# 2d.net
KiCad netlist of a schematic drawn in EAGLE
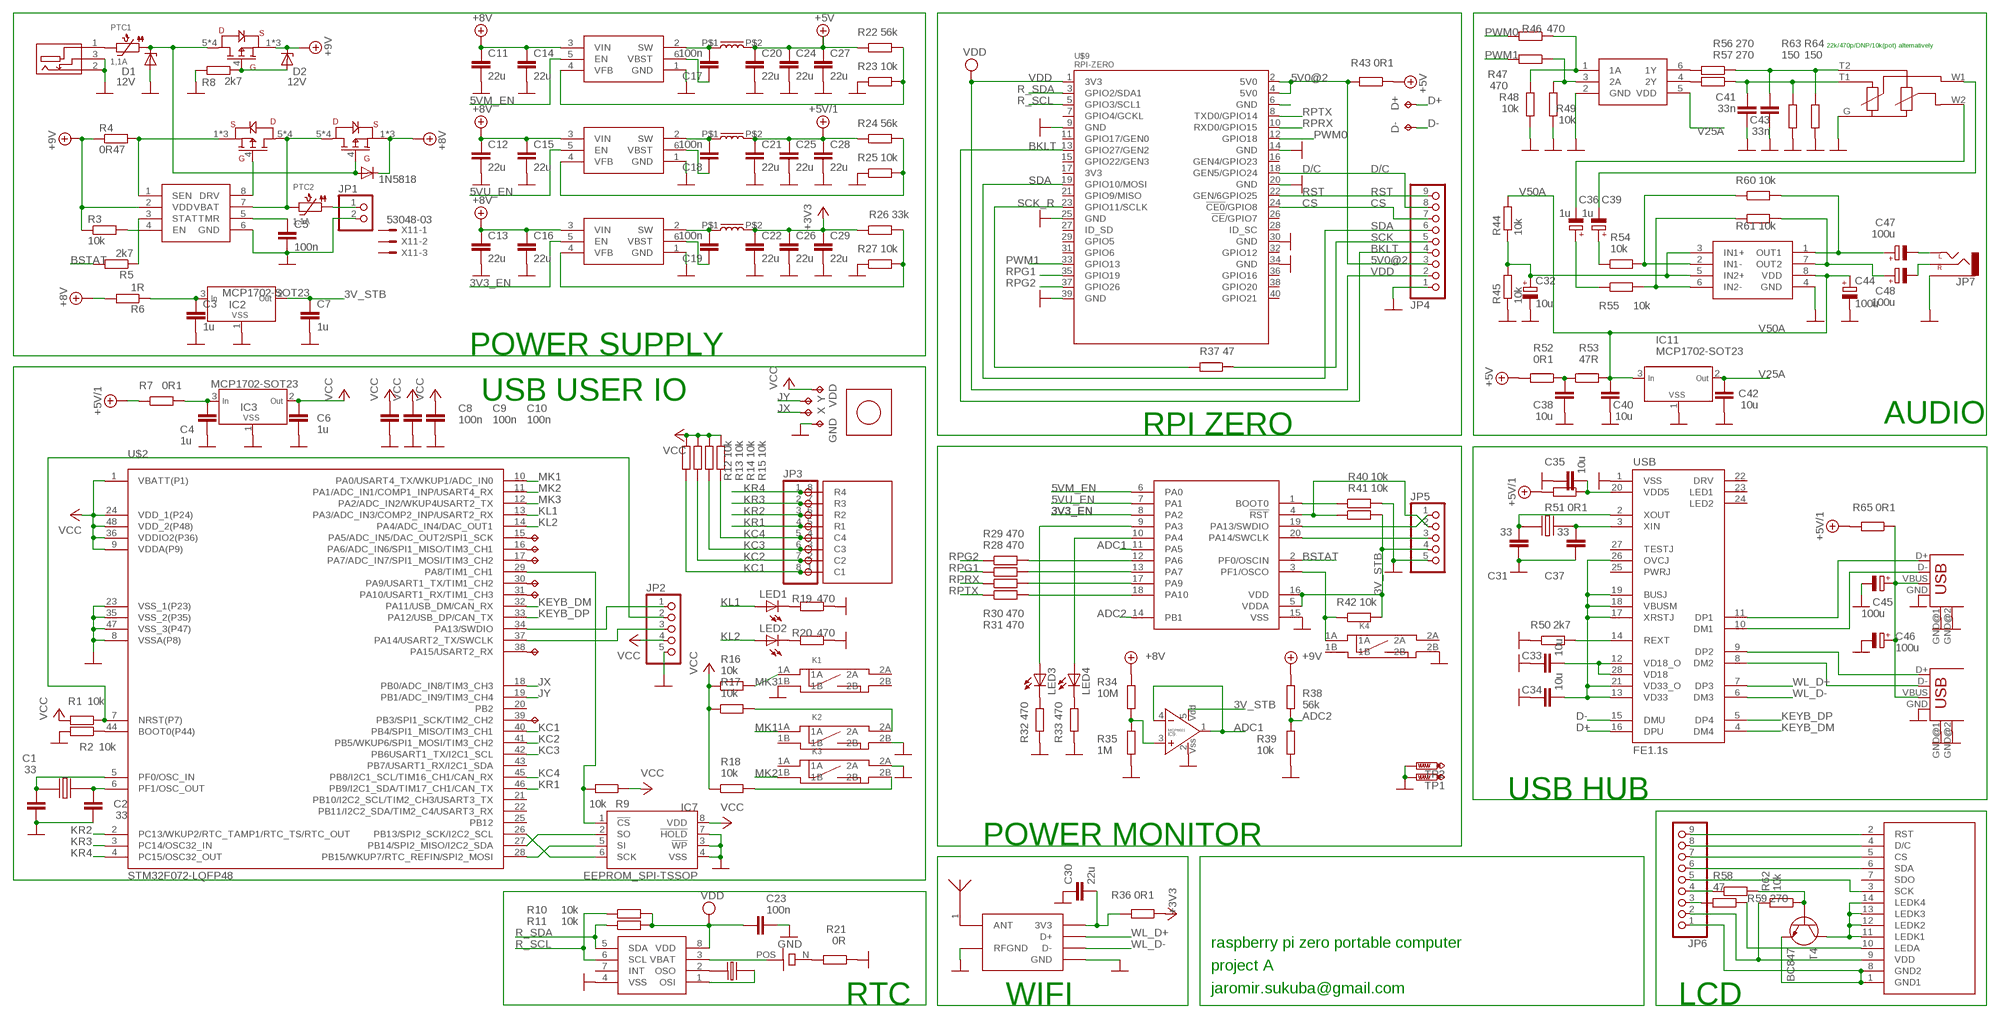
[diagram p0: schematic, sheet 1]

(export (version "E")
  (design (tool "Eeschema 10.0.6"))
  (components
    (comp (ref "ANT1")
      (value "ANT_RAINSUN_24GHZ")
      (footprint "eagle-import:ANT_RAINSUN-24G")
      (libsource (lib "eagle-import") (part "ANT_RAINSUN_24GHZ"))
    )
    (comp (ref "C1")
      (value "33")
      (footprint "eagle-import:R0805")
      (libsource (lib "eagle-import") (part "C_0806"))
    )
    (comp (ref "C2")
      (value "33")
      (footprint "eagle-import:R0805")
      (libsource (lib "eagle-import") (part "C_0806"))
    )
    (comp (ref "C3")
      (value "1u")
      (footprint "eagle-import:R0805")
      (libsource (lib "eagle-import") (part "C_0806"))
    )
    (comp (ref "C4")
      (value "1u")
      (footprint "eagle-import:R0805")
      (libsource (lib "eagle-import") (part "C_0806"))
    )
    (comp (ref "C5")
      (value "100n")
      (footprint "eagle-import:R0805")
      (libsource (lib "eagle-import") (part "C_0806"))
    )
    (comp (ref "C6")
      (value "1u")
      (footprint "eagle-import:R0805")
      (libsource (lib "eagle-import") (part "C_0806"))
    )
    (comp (ref "C7")
      (value "1u")
      (footprint "eagle-import:R0805")
      (libsource (lib "eagle-import") (part "C_0806"))
    )
    (comp (ref "C8")
      (value "100n")
      (footprint "eagle-import:R0805")
      (libsource (lib "eagle-import") (part "C_0806"))
    )
    (comp (ref "C9")
      (value "100n")
      (footprint "eagle-import:R0805")
      (libsource (lib "eagle-import") (part "C_0806"))
    )
    (comp (ref "C10")
      (value "100n")
      (footprint "eagle-import:R0805")
      (libsource (lib "eagle-import") (part "C_0806"))
    )
    (comp (ref "C11")
      (value "22u")
      (footprint "eagle-import:R0805")
      (libsource (lib "eagle-import") (part "C_0806"))
    )
    (comp (ref "C12")
      (value "22u")
      (footprint "eagle-import:R0805")
      (libsource (lib "eagle-import") (part "C_0806"))
    )
    (comp (ref "C13")
      (value "22u")
      (footprint "eagle-import:R0805")
      (libsource (lib "eagle-import") (part "C_0806"))
    )
    (comp (ref "C14")
      (value "22u")
      (footprint "eagle-import:R0805")
      (libsource (lib "eagle-import") (part "C_0806"))
    )
    (comp (ref "C15")
      (value "22u")
      (footprint "eagle-import:R0805")
      (libsource (lib "eagle-import") (part "C_0806"))
    )
    (comp (ref "C16")
      (value "22u")
      (footprint "eagle-import:R0805")
      (libsource (lib "eagle-import") (part "C_0806"))
    )
    (comp (ref "C17")
      (value "100n")
      (footprint "eagle-import:R0805")
      (libsource (lib "eagle-import") (part "C_0806"))
    )
    (comp (ref "C18")
      (value "100n")
      (footprint "eagle-import:R0805")
      (libsource (lib "eagle-import") (part "C_0806"))
    )
    (comp (ref "C19")
      (value "100n")
      (footprint "eagle-import:R0805")
      (libsource (lib "eagle-import") (part "C_0806"))
    )
    (comp (ref "C20")
      (value "22u")
      (footprint "eagle-import:R0805")
      (libsource (lib "eagle-import") (part "C_0806"))
    )
    (comp (ref "C21")
      (value "22u")
      (footprint "eagle-import:R0805")
      (libsource (lib "eagle-import") (part "C_0806"))
    )
    (comp (ref "C22")
      (value "22u")
      (footprint "eagle-import:R0805")
      (libsource (lib "eagle-import") (part "C_0806"))
    )
    (comp (ref "C23")
      (value "100n")
      (footprint "eagle-import:R0805")
      (libsource (lib "eagle-import") (part "C_0806"))
    )
    (comp (ref "C24")
      (value "22u")
      (footprint "eagle-import:R0805")
      (libsource (lib "eagle-import") (part "C_0806"))
    )
    (comp (ref "C25")
      (value "22u")
      (footprint "eagle-import:R0805")
      (libsource (lib "eagle-import") (part "C_0806"))
    )
    (comp (ref "C26")
      (value "22u")
      (footprint "eagle-import:R0805")
      (libsource (lib "eagle-import") (part "C_0806"))
    )
    (comp (ref "C27")
      (value "22u")
      (footprint "eagle-import:R0805")
      (libsource (lib "eagle-import") (part "C_0806"))
    )
    (comp (ref "C28")
      (value "22u")
      (footprint "eagle-import:R0805")
      (libsource (lib "eagle-import") (part "C_0806"))
    )
    (comp (ref "C29")
      (value "22u")
      (footprint "eagle-import:R0805")
      (libsource (lib "eagle-import") (part "C_0806"))
    )
    (comp (ref "C30")
      (value "22u")
      (footprint "eagle-import:R0805")
      (libsource (lib "eagle-import") (part "C_0806"))
    )
    (comp (ref "C31")
      (value "33")
      (footprint "eagle-import:R0805")
      (libsource (lib "eagle-import") (part "C_0806"))
    )
    (comp (ref "C32")
      (value "10u")
      (footprint "eagle-import:PANASONIC_B")
      (libsource (lib "eagle-import") (part "CPOL-EUB"))
    )
    (comp (ref "C33")
      (value "10u")
      (footprint "eagle-import:R0805")
      (libsource (lib "eagle-import") (part "C_0806"))
    )
    (comp (ref "C34")
      (value "10u")
      (footprint "eagle-import:R0805")
      (libsource (lib "eagle-import") (part "C_0806"))
    )
    (comp (ref "C35")
      (value "10u")
      (footprint "eagle-import:R0805")
      (libsource (lib "eagle-import") (part "C_0806"))
    )
    (comp (ref "C36")
      (value "1u")
      (footprint "eagle-import:PANASONIC_A")
      (libsource (lib "eagle-import") (part "CPOL-EUA"))
    )
    (comp (ref "C37")
      (value "33")
      (footprint "eagle-import:R0805")
      (libsource (lib "eagle-import") (part "C_0806"))
    )
    (comp (ref "C38")
      (value "10u")
      (footprint "eagle-import:R0805")
      (libsource (lib "eagle-import") (part "C_0806"))
    )
    (comp (ref "C39")
      (value "1u")
      (footprint "eagle-import:PANASONIC_A")
      (libsource (lib "eagle-import") (part "CPOL-EUA"))
    )
    (comp (ref "C40")
      (value "10u")
      (footprint "eagle-import:R0805")
      (libsource (lib "eagle-import") (part "C_0806"))
    )
    (comp (ref "C41")
      (value "33n")
      (footprint "eagle-import:R0805")
      (libsource (lib "eagle-import") (part "C_0806"))
    )
    (comp (ref "C42")
      (value "10u")
      (footprint "eagle-import:R0805")
      (libsource (lib "eagle-import") (part "C_0806"))
    )
    (comp (ref "C43")
      (value "33n")
      (footprint "eagle-import:R0805")
      (libsource (lib "eagle-import") (part "C_0806"))
    )
    (comp (ref "C44")
      (value "100u")
      (footprint "eagle-import:PANASONIC_D")
      (libsource (lib "eagle-import") (part "CPOL-EUD"))
    )
    (comp (ref "C45")
      (value "100u")
      (footprint "eagle-import:PANASONIC_D")
      (libsource (lib "eagle-import") (part "CPOL-EUD"))
    )
    (comp (ref "C46")
      (value "100u")
      (footprint "eagle-import:PANASONIC_D")
      (libsource (lib "eagle-import") (part "CPOL-EUD"))
    )
    (comp (ref "C47")
      (value "100u")
      (footprint "eagle-import:PANASONIC_D")
      (libsource (lib "eagle-import") (part "CPOL-EUD"))
    )
    (comp (ref "C48")
      (value "100u")
      (footprint "eagle-import:PANASONIC_D")
      (libsource (lib "eagle-import") (part "CPOL-EUD"))
    )
    (comp (ref "D+")
      (value "TPTP14R")
      (footprint "eagle-import:TP14R")
      (libsource (lib "eagle-import") (part "TPTP14R"))
    )
    (comp (ref "D-")
      (value "TPTP14R")
      (footprint "eagle-import:TP14R")
      (libsource (lib "eagle-import") (part "TPTP14R"))
    )
    (comp (ref "D1")
      (value "12V")
      (footprint "eagle-import:SMB")
      (libsource (lib "eagle-import") (part "ZENER-DIODESMB"))
    )
    (comp (ref "D2")
      (value "12V")
      (footprint "eagle-import:SOD80C")
      (libsource (lib "eagle-import") (part "ZENER-DIODESOD80C"))
    )
    (comp (ref "D3")
      (value "1N5818")
      (footprint "eagle-import:SMB")
      (libsource (lib "eagle-import") (part "DIODE-SMB"))
    )
    (comp (ref "GND")
      (value "TPTP14R")
      (footprint "eagle-import:TP14R")
      (libsource (lib "eagle-import") (part "TPTP14R"))
    )
    (comp (ref "IC1")
      (value "MCP73844")
      (footprint "eagle-import:MSOP8")
      (libsource (lib "eagle-import") (part "MCP73844"))
    )
    (comp (ref "IC2")
      (value "MCP1702-SOT23")
      (footprint "eagle-import:SOT23")
      (libsource (lib "eagle-import") (part "MCP1702-SOT23"))
    )
    (comp (ref "IC3")
      (value "MCP1702-SOT23")
      (footprint "eagle-import:SOT23")
      (libsource (lib "eagle-import") (part "MCP1702-SOT23"))
    )
    (comp (ref "IC4")
      (value "TPS562200")
      (footprint "eagle-import:SOT23-6")
      (libsource (lib "eagle-import") (part "TPS562200"))
    )
    (comp (ref "IC5")
      (value "TPS562200")
      (footprint "eagle-import:SOT23-6")
      (libsource (lib "eagle-import") (part "TPS562200"))
    )
    (comp (ref "IC6")
      (value "TPS562200")
      (footprint "eagle-import:SOT23-6")
      (libsource (lib "eagle-import") (part "TPS562200"))
    )
    (comp (ref "IC7")
      (value "EEPROM_SPI-TSSOP")
      (footprint "eagle-import:TSSOP8W")
      (libsource (lib "eagle-import") (part "EEPROM_SPI-TSSOP"))
    )
    (comp (ref "IC8")
      (value "PCF8523")
      (footprint "eagle-import:SO-08")
      (libsource (lib "eagle-import") (part "PCF8523"))
    )
    (comp (ref "IC9")
      (value "MCP6021")
      (footprint "eagle-import:SOT23-5L")
      (libsource (lib "eagle-import") (part "MCP6021"))
    )
    (comp (ref "IC10")
      (value "74LVC2G34")
      (footprint "eagle-import:SOT23-6")
      (libsource (lib "eagle-import") (part "74LVC2G34"))
    )
    (comp (ref "IC11")
      (value "MCP1702-SOT23")
      (footprint "eagle-import:SOT23")
      (libsource (lib "eagle-import") (part "MCP1702-SOT23"))
    )
    (comp (ref "JP1")
      (value "PINHD-1X02_2.54-90°")
      (footprint "eagle-import:1X02_90")
      (libsource (lib "eagle-import") (part "PINHD-1X02_2.54-90°"))
    )
    (comp (ref "JP2")
      (value "PINHD-1X05_2.54-90°")
      (footprint "eagle-import:1X05_90")
      (libsource (lib "eagle-import") (part "PINHD-1X05_2.54-90°"))
    )
    (comp (ref "JP3")
      (value "PINHD-1X08_2.54")
      (footprint "eagle-import:1X08")
      (libsource (lib "eagle-import") (part "PINHD-1X08_2.54"))
    )
    (comp (ref "JP4")
      (value "PINHD-1X09_2.00")
      (footprint "eagle-import:1X09M")
      (libsource (lib "eagle-import") (part "PINHD-1X09_2.00"))
    )
    (comp (ref "JP5")
      (value "PINHD-1X05_2.54-90°")
      (footprint "eagle-import:1X05_90")
      (libsource (lib "eagle-import") (part "PINHD-1X05_2.54-90°"))
    )
    (comp (ref "JP6")
      (value "PINHD-1X09_2.00")
      (footprint "eagle-import:1X09M")
      (libsource (lib "eagle-import") (part "PINHD-1X09_2.00"))
    )
    (comp (ref "JP7")
      (value "AUDIO-JACKPTH")
      (footprint "eagle-import:AUDIO-JACK")
      (libsource (lib "eagle-import") (part "AUDIO-JACKPTH"))
    )
    (comp (ref "K1")
      (value "SWITCH_BD_B")
      (footprint "eagle-import:SW_SMD2")
      (libsource (lib "eagle-import") (part "SWITCH_BD_B"))
    )
    (comp (ref "K2")
      (value "SWITCH_BD_B")
      (footprint "eagle-import:SW_SMD2")
      (libsource (lib "eagle-import") (part "SWITCH_BD_B"))
    )
    (comp (ref "K3")
      (value "SWITCH_BD_B")
      (footprint "eagle-import:SW_SMD2")
      (libsource (lib "eagle-import") (part "SWITCH_BD_B"))
    )
    (comp (ref "K4")
      (value "SWITCH_BD_B")
      (footprint "eagle-import:SW_SMD2")
      (libsource (lib "eagle-import") (part "SWITCH_BD_B"))
    )
    (comp (ref "LED1")
      (value "LED3MM")
      (footprint "eagle-import:LED3MM")
      (libsource (lib "eagle-import") (part "LED3MM"))
    )
    (comp (ref "LED2")
      (value "LED3MM")
      (footprint "eagle-import:LED3MM")
      (libsource (lib "eagle-import") (part "LED3MM"))
    )
    (comp (ref "LED3")
      (value "LED3MM")
      (footprint "eagle-import:LED3MM")
      (libsource (lib "eagle-import") (part "LED3MM"))
    )
    (comp (ref "LED4")
      (value "LED3MM")
      (footprint "eagle-import:LED3MM")
      (libsource (lib "eagle-import") (part "LED3MM"))
    )
    (comp (ref "MOD1")
      (value "MOD_USB_RTL8188")
      (footprint "eagle-import:MOD_USB_RTL8188")
      (libsource (lib "eagle-import") (part "MOD_USB_RTL8188"))
    )
    (comp (ref "PTC1")
      (value "1,1A")
      (footprint "eagle-import:PTC1812")
      (libsource (lib "eagle-import") (part "PTC1812"))
    )
    (comp (ref "PTC2")
      (value "1,1A")
      (footprint "eagle-import:PTC1812")
      (libsource (lib "eagle-import") (part "PTC1812"))
    )
    (comp (ref "Q1")
      (value "CRYSTAL87X38")
      (footprint "eagle-import:CRYST_32K_87X38MM")
      (libsource (lib "eagle-import") (part "CRYSTAL87X38"))
    )
    (comp (ref "R1")
      (value "10k")
      (footprint "eagle-import:R0805")
      (libsource (lib "eagle-import") (part "R_0805"))
    )
    (comp (ref "R2")
      (value "10k")
      (footprint "eagle-import:R0805")
      (libsource (lib "eagle-import") (part "R_0805"))
    )
    (comp (ref "R3")
      (value "10k")
      (footprint "eagle-import:R0805")
      (libsource (lib "eagle-import") (part "R_0805"))
    )
    (comp (ref "R4")
      (value "0R47")
      (footprint "eagle-import:R1206")
      (libsource (lib "eagle-import") (part "R_1206"))
    )
    (comp (ref "R5")
      (value "2k7")
      (footprint "eagle-import:R0805")
      (libsource (lib "eagle-import") (part "R_0805"))
    )
    (comp (ref "R6")
      (value "1R")
      (footprint "eagle-import:R0805")
      (libsource (lib "eagle-import") (part "R_0805"))
    )
    (comp (ref "R7")
      (value "0R1")
      (footprint "eagle-import:R1206")
      (libsource (lib "eagle-import") (part "R_1206"))
    )
    (comp (ref "R8")
      (value "2k7")
      (footprint "eagle-import:R0805")
      (libsource (lib "eagle-import") (part "R_0805"))
    )
    (comp (ref "R9")
      (value "10k")
      (footprint "eagle-import:R0805")
      (libsource (lib "eagle-import") (part "R_0805"))
    )
    (comp (ref "R10")
      (value "10k")
      (footprint "eagle-import:R0805")
      (libsource (lib "eagle-import") (part "R_0805"))
    )
    (comp (ref "R11")
      (value "10k")
      (footprint "eagle-import:R0805")
      (libsource (lib "eagle-import") (part "R_0805"))
    )
    (comp (ref "R12")
      (value "10k")
      (footprint "eagle-import:R0805")
      (libsource (lib "eagle-import") (part "R_0805"))
    )
    (comp (ref "R13")
      (value "10k")
      (footprint "eagle-import:R0805")
      (libsource (lib "eagle-import") (part "R_0805"))
    )
    (comp (ref "R14")
      (value "10k")
      (footprint "eagle-import:R0805")
      (libsource (lib "eagle-import") (part "R_0805"))
    )
    (comp (ref "R15")
      (value "10k")
      (footprint "eagle-import:R0805")
      (libsource (lib "eagle-import") (part "R_0805"))
    )
    (comp (ref "R16")
      (value "10k")
      (footprint "eagle-import:R0805")
      (libsource (lib "eagle-import") (part "R_0805"))
    )
    (comp (ref "R17")
      (value "10k")
      (footprint "eagle-import:R0805")
      (libsource (lib "eagle-import") (part "R_0805"))
    )
    (comp (ref "R18")
      (value "10k")
      (footprint "eagle-import:R0805")
      (libsource (lib "eagle-import") (part "R_0805"))
    )
    (comp (ref "R19")
      (value "470")
      (footprint "eagle-import:R0805")
      (libsource (lib "eagle-import") (part "R_0805"))
    )
    (comp (ref "R20")
      (value "470")
      (footprint "eagle-import:R0805")
      (libsource (lib "eagle-import") (part "R_0805"))
    )
    (comp (ref "R21")
      (value "0R")
      (footprint "eagle-import:R0805")
      (libsource (lib "eagle-import") (part "R_0805"))
    )
    (comp (ref "R22")
      (value "56k")
      (footprint "eagle-import:R0805")
      (libsource (lib "eagle-import") (part "R_0805"))
    )
    (comp (ref "R23")
      (value "10k")
      (footprint "eagle-import:R0805")
      (libsource (lib "eagle-import") (part "R_0805"))
    )
    (comp (ref "R24")
      (value "56k")
      (footprint "eagle-import:R0805")
      (libsource (lib "eagle-import") (part "R_0805"))
    )
    (comp (ref "R25")
      (value "10k")
      (footprint "eagle-import:R0805")
      (libsource (lib "eagle-import") (part "R_0805"))
    )
    (comp (ref "R26")
      (value "33k")
      (footprint "eagle-import:R0805")
      (libsource (lib "eagle-import") (part "R_0805"))
    )
    (comp (ref "R27")
      (value "10k")
      (footprint "eagle-import:R0805")
      (libsource (lib "eagle-import") (part "R_0805"))
    )
    (comp (ref "R28")
      (value "470")
      (footprint "eagle-import:R0805")
      (libsource (lib "eagle-import") (part "R_0805"))
    )
    (comp (ref "R29")
      (value "470")
      (footprint "eagle-import:R0805")
      (libsource (lib "eagle-import") (part "R_0805"))
    )
    (comp (ref "R30")
      (value "470")
      (footprint "eagle-import:R0805")
      (libsource (lib "eagle-import") (part "R_0805"))
    )
    (comp (ref "R31")
      (value "470")
      (footprint "eagle-import:R0805")
      (libsource (lib "eagle-import") (part "R_0805"))
    )
    (comp (ref "R32")
      (value "470")
      (footprint "eagle-import:R0805")
      (libsource (lib "eagle-import") (part "R_0805"))
    )
    (comp (ref "R33")
      (value "470")
      (footprint "eagle-import:R0805")
      (libsource (lib "eagle-import") (part "R_0805"))
    )
    (comp (ref "R34")
      (value "10M")
      (footprint "eagle-import:R0805")
      (libsource (lib "eagle-import") (part "R_0805"))
    )
    (comp (ref "R35")
      (value "1M")
      (footprint "eagle-import:R0805")
      (libsource (lib "eagle-import") (part "R_0805"))
    )
    (comp (ref "R36")
      (value "0R1")
      (footprint "eagle-import:R1206")
      (libsource (lib "eagle-import") (part "R_1206"))
    )
    (comp (ref "R37")
      (value "47")
      (footprint "eagle-import:R0805")
      (libsource (lib "eagle-import") (part "R_0805"))
    )
    (comp (ref "R38")
      (value "56k")
      (footprint "eagle-import:R0805")
      (libsource (lib "eagle-import") (part "R_0805"))
    )
    (comp (ref "R39")
      (value "10k")
      (footprint "eagle-import:R0805")
      (libsource (lib "eagle-import") (part "R_0805"))
    )
    (comp (ref "R40")
      (value "10k")
      (footprint "eagle-import:R0805")
      (libsource (lib "eagle-import") (part "R_0805"))
    )
    (comp (ref "R41")
      (value "10k")
      (footprint "eagle-import:R0805")
      (libsource (lib "eagle-import") (part "R_0805"))
    )
    (comp (ref "R42")
      (value "10k")
      (footprint "eagle-import:R0805")
      (libsource (lib "eagle-import") (part "R_0805"))
    )
    (comp (ref "R43")
      (value "0R1")
      (footprint "eagle-import:R1206")
      (libsource (lib "eagle-import") (part "R_1206"))
    )
    (comp (ref "R44")
      (value "10k")
      (footprint "eagle-import:R0805")
      (libsource (lib "eagle-import") (part "R_0805"))
    )
    (comp (ref "R45")
      (value "10k")
      (footprint "eagle-import:R0805")
      (libsource (lib "eagle-import") (part "R_0805"))
    )
    (comp (ref "R46")
      (value "470")
      (footprint "eagle-import:R0805")
      (libsource (lib "eagle-import") (part "R_0805"))
    )
    (comp (ref "R47")
      (value "470")
      (footprint "eagle-import:R0805")
      (libsource (lib "eagle-import") (part "R_0805"))
    )
    (comp (ref "R48")
      (value "10k")
      (footprint "eagle-import:R0805")
      (libsource (lib "eagle-import") (part "R_0805"))
    )
    (comp (ref "R49")
      (value "10k")
      (footprint "eagle-import:R0805")
      (libsource (lib "eagle-import") (part "R_0805"))
    )
    (comp (ref "R50")
      (value "2k7")
      (footprint "eagle-import:R0805")
      (libsource (lib "eagle-import") (part "R_0805"))
    )
    (comp (ref "R51")
      (value "0R1")
      (footprint "eagle-import:R1206")
      (libsource (lib "eagle-import") (part "R_1206"))
    )
    (comp (ref "R52")
      (value "0R1")
      (footprint "eagle-import:R1206")
      (libsource (lib "eagle-import") (part "R_1206"))
    )
    (comp (ref "R53")
      (value "47R")
      (footprint "eagle-import:R0805")
      (libsource (lib "eagle-import") (part "R_0805"))
    )
    (comp (ref "R54")
      (value "10k")
      (footprint "eagle-import:R0805")
      (libsource (lib "eagle-import") (part "R_0805"))
    )
    (comp (ref "R55")
      (value "10k")
      (footprint "eagle-import:R0805")
      (libsource (lib "eagle-import") (part "R_0805"))
    )
    (comp (ref "R56")
      (value "270")
      (footprint "eagle-import:R0805")
      (libsource (lib "eagle-import") (part "R_0805"))
    )
    (comp (ref "R57")
      (value "270")
      (footprint "eagle-import:R0805")
      (libsource (lib "eagle-import") (part "R_0805"))
    )
    (comp (ref "R58")
      (value "47")
      (footprint "eagle-import:R0805")
      (libsource (lib "eagle-import") (part "R_0805"))
    )
    (comp (ref "R59")
      (value "270")
      (footprint "eagle-import:R0805")
      (libsource (lib "eagle-import") (part "R_0805"))
    )
    (comp (ref "R60")
      (value "10k")
      (footprint "eagle-import:R0805")
      (libsource (lib "eagle-import") (part "R_0805"))
    )
    (comp (ref "R61")
      (value "10k")
      (footprint "eagle-import:R0805")
      (libsource (lib "eagle-import") (part "R_0805"))
    )
    (comp (ref "R62")
      (value "10k")
      (footprint "eagle-import:R0805")
      (libsource (lib "eagle-import") (part "R_0805"))
    )
    (comp (ref "R63")
      (value "150")
      (footprint "eagle-import:R0805")
      (libsource (lib "eagle-import") (part "R_0805"))
    )
    (comp (ref "R64")
      (value "150")
      (footprint "eagle-import:R0805")
      (libsource (lib "eagle-import") (part "R_0805"))
    )
    (comp (ref "R65")
      (value "0R1")
      (footprint "eagle-import:R1206")
      (libsource (lib "eagle-import") (part "R_1206"))
    )
    (comp (ref "T1")
      (value "PFET_SO8")
      (footprint "eagle-import:SO-08")
      (libsource (lib "eagle-import") (part "PFET_SO8"))
    )
    (comp (ref "T2")
      (value "PFET_SO8")
      (footprint "eagle-import:SO-08")
      (libsource (lib "eagle-import") (part "PFET_SO8"))
    )
    (comp (ref "T3")
      (value "PFET_SO8")
      (footprint "eagle-import:SO-08")
      (libsource (lib "eagle-import") (part "PFET_SO8"))
    )
    (comp (ref "T4")
      (value "BC847")
      (footprint "eagle-import:SOT23")
      (libsource (lib "eagle-import") (part "BC847"))
    )
    (comp (ref "TFT1")
      (value "DISP_ILI_28")
      (footprint "eagle-import:DISP_ILI_28")
      (libsource (lib "eagle-import") (part "DISP_ILI_28"))
    )
    (comp (ref "TP1")
      (value "PTR1PAD1-13")
      (footprint "eagle-import:P1-13")
      (libsource (lib "eagle-import") (part "PTR1PAD1-13"))
    )
    (comp (ref "TP2")
      (value "PTR1PAD1-13")
      (footprint "eagle-import:P1-13")
      (libsource (lib "eagle-import") (part "PTR1PAD1-13"))
    )
    (comp (ref "U$1")
      (value "CONN_DC_13")
      (footprint "eagle-import:CON_DC13")
      (libsource (lib "eagle-import") (part "CONN_DC_13"))
    )
    (comp (ref "U$2")
      (value "STM32F072-LQFP48")
      (footprint "eagle-import:LQFP48")
      (libsource (lib "eagle-import") (part "STM32F072-LQFP48"))
    )
    (comp (ref "U$3")
      (value "2u2")
      (footprint "eagle-import:BOURNS_SRP7030")
      (libsource (lib "eagle-import") (part "INDUCTORBOURNS_SRP7030"))
    )
    (comp (ref "U$4")
      (value "2u2")
      (footprint "eagle-import:BOURNS_SRP7030")
      (libsource (lib "eagle-import") (part "INDUCTORBOURNS_SRP7030"))
    )
    (comp (ref "U$5")
      (value "2u2")
      (footprint "eagle-import:BOURNS_SRP7030")
      (libsource (lib "eagle-import") (part "INDUCTORBOURNS_SRP7030"))
    )
    (comp (ref "U$6")
      (value "BATTH1220")
      (footprint "eagle-import:BATT_HOLDER_DS1092-12")
      (libsource (lib "eagle-import") (part "BATTH1220"))
    )
    (comp (ref "U$7")
      (value "KB1604")
      (footprint "eagle-import:KB1604")
      (libsource (lib "eagle-import") (part "KB1604"))
    )
    (comp (ref "U$8")
      (value "JOY_PS")
      (footprint "eagle-import:JOY_PS")
      (libsource (lib "eagle-import") (part "JOY_PS"))
    )
    (comp (ref "U$9")
      (value "RPI-ZERO")
      (footprint "eagle-import:RASPBERRYPI_BASTELSTUBE_V13_RASPI_BOARD_B+_FULL")
      (libsource (lib "eagle-import") (part "RPI-ZERO"))
    )
    (comp (ref "U$10")
      (value "STM32F030_20")
      (footprint "eagle-import:TSSOP20")
      (libsource (lib "eagle-import") (part "STM32F030_20"))
    )
    (comp (ref "U$11")
      (value "TDA1308")
      (footprint "eagle-import:SO-08")
      (libsource (lib "eagle-import") (part "TDA1308"))
    )
    (comp (ref "U$12")
      (value "POT_DUAL_14X2")
      (footprint "eagle-import:POT_14X2DUAL")
      (libsource (lib "eagle-import") (part "POT_DUAL_14X2"))
    )
    (comp (ref "USB")
      (value "FE1.1S")
      (footprint "eagle-import:FE1.1S_SSOP-28")
      (libsource (lib "eagle-import") (part "FE1.1S"))
    )
    (comp (ref "USB1")
      (value "USB-A-S")
      (footprint "eagle-import:USB-A-S")
      (libsource (lib "eagle-import") (part "USB-A-S"))
    )
    (comp (ref "USB2")
      (value "USB-A-S")
      (footprint "eagle-import:USB-A-S")
      (libsource (lib "eagle-import") (part "USB-A-S"))
    )
    (comp (ref "VDD")
      (value "TPTP14R")
      (footprint "eagle-import:TP14R")
      (libsource (lib "eagle-import") (part "TPTP14R"))
    )
    (comp (ref "X")
      (value "TPTP14R")
      (footprint "eagle-import:TP14R")
      (libsource (lib "eagle-import") (part "TPTP14R"))
    )
    (comp (ref "X1")
      (value "CRYST_TC26SMXAS")
      (footprint "eagle-import:CR_12SMXA_S")
      (libsource (lib "eagle-import") (part "CRYST_TC26SMXAS"))
    )
    (comp (ref "X2")
      (value "TPTP14R")
      (footprint "eagle-import:TP14R")
      (libsource (lib "eagle-import") (part "TPTP14R"))
    )
    (comp (ref "X3")
      (value "TPTP14R")
      (footprint "eagle-import:TP14R")
      (libsource (lib "eagle-import") (part "TPTP14R"))
    )
    (comp (ref "X4")
      (value "TPTP14R")
      (footprint "eagle-import:TP14R")
      (libsource (lib "eagle-import") (part "TPTP14R"))
    )
    (comp (ref "X5")
      (value "TPTP14R")
      (footprint "eagle-import:TP14R")
      (libsource (lib "eagle-import") (part "TPTP14R"))
    )
    (comp (ref "X6")
      (value "TPTP14R")
      (footprint "eagle-import:TP14R")
      (libsource (lib "eagle-import") (part "TPTP14R"))
    )
    (comp (ref "X7")
      (value "TPTP14R")
      (footprint "eagle-import:TP14R")
      (libsource (lib "eagle-import") (part "TPTP14R"))
    )
    (comp (ref "X8")
      (value "TPTP14R")
      (footprint "eagle-import:TP14R")
      (libsource (lib "eagle-import") (part "TPTP14R"))
    )
    (comp (ref "X9")
      (value "CRYST_TC26SMXAS")
      (footprint "eagle-import:CR_12SMXA_S")
      (libsource (lib "eagle-import") (part "CRYST_TC26SMXAS"))
    )
    (comp (ref "X11")
      (value "53048-03")
      (footprint "eagle-import:53048-03")
      (fields (field (name "MF") "WALDOM/MOLEX") (field (name "MPN") "53048-0310"))
      (libsource (lib "eagle-import") (part "53?-03048"))
    )
    (comp (ref "Y")
      (value "TPTP14R")
      (footprint "eagle-import:TP14R")
      (libsource (lib "eagle-import") (part "TPTP14R"))
    )
  )
  (nets
    (net (code "1") (name "+3V3") (class "Default")
      (node (ref "C22") (pin "1") (pinfunction "1_1") (pintype "passive"))
      (node (ref "C26") (pin "1") (pinfunction "1_1") (pintype "passive"))
      (node (ref "C29") (pin "1") (pinfunction "1_1") (pintype "passive"))
      (node (ref "R26") (pin "1") (pinfunction "1_1") (pintype "passive"))
      (node (ref "R36") (pin "1") (pinfunction "1_1") (pintype "passive"))
      (node (ref "U$5") (pin "P$2") (pinfunction "P$2_P$2") (pintype "bidirectional"))
    )
    (net (code "2") (name "+5V") (class "Default")
      (node (ref "C20") (pin "1") (pinfunction "1_1") (pintype "passive"))
      (node (ref "C24") (pin "1") (pinfunction "1_1") (pintype "passive"))
      (node (ref "C27") (pin "1") (pinfunction "1_1") (pintype "passive"))
      (node (ref "R22") (pin "1") (pinfunction "1_1") (pintype "passive"))
      (node (ref "R43") (pin "1") (pinfunction "1_1") (pintype "passive"))
      (node (ref "R52") (pin "2") (pinfunction "2_2") (pintype "passive"))
      (node (ref "U$3") (pin "P$2") (pinfunction "P$2_P$2") (pintype "bidirectional"))
    )
    (net (code "3") (name "+5V{slash}1") (class "Default")
      (node (ref "C21") (pin "1") (pinfunction "1_1") (pintype "passive"))
      (node (ref "C25") (pin "1") (pinfunction "1_1") (pintype "passive"))
      (node (ref "C28") (pin "1") (pinfunction "1_1") (pintype "passive"))
      (node (ref "R24") (pin "1") (pinfunction "1_1") (pintype "passive"))
      (node (ref "R51") (pin "2") (pinfunction "2_2") (pintype "passive"))
      (node (ref "R65") (pin "2") (pinfunction "2_2") (pintype "passive"))
      (node (ref "R7") (pin "1") (pinfunction "1_1") (pintype "passive"))
      (node (ref "U$4") (pin "P$2") (pinfunction "P$2_P$2") (pintype "bidirectional"))
    )
    (net (code "4") (name "+8V") (class "Default")
      (node (ref "C11") (pin "1") (pinfunction "1_1") (pintype "passive"))
      (node (ref "C12") (pin "1") (pinfunction "1_1") (pintype "passive"))
      (node (ref "C13") (pin "1") (pinfunction "1_1") (pintype "passive"))
      (node (ref "C14") (pin "1") (pinfunction "1_1") (pintype "passive"))
      (node (ref "C15") (pin "1") (pinfunction "1_1") (pintype "passive"))
      (node (ref "C16") (pin "1") (pinfunction "1_1") (pintype "passive"))
      (node (ref "D3") (pin "C") (pinfunction "C_C") (pintype "passive"))
      (node (ref "IC4") (pin "3") (pinfunction "VIN_3") (pintype "bidirectional"))
      (node (ref "IC5") (pin "3") (pinfunction "VIN_3") (pintype "bidirectional"))
      (node (ref "IC6") (pin "3") (pinfunction "VIN_3") (pintype "bidirectional"))
      (node (ref "R34") (pin "2") (pinfunction "2_2") (pintype "passive"))
      (node (ref "R6") (pin "2") (pinfunction "2_2") (pintype "passive"))
      (node (ref "T3") (pin "1") (pinfunction "S_1") (pintype "bidirectional"))
      (node (ref "T3") (pin "2") (pinfunction "S_2") (pintype "bidirectional"))
      (node (ref "T3") (pin "3") (pinfunction "S_3") (pintype "bidirectional"))
    )
    (net (code "5") (name "+9V") (class "Default")
      (node (ref "D2") (pin "C") (pinfunction "C_C") (pintype "passive"))
      (node (ref "IC1") (pin "2") (pinfunction "VDD_2") (pintype "bidirectional"))
      (node (ref "R3") (pin "1") (pinfunction "1_1") (pintype "passive"))
      (node (ref "R38") (pin "2") (pinfunction "2_2") (pintype "passive"))
      (node (ref "R4") (pin "1") (pinfunction "1_1") (pintype "passive"))
      (node (ref "T1") (pin "1") (pinfunction "S_1") (pintype "bidirectional"))
      (node (ref "T1") (pin "2") (pinfunction "S_2") (pintype "bidirectional"))
      (node (ref "T1") (pin "3") (pinfunction "S_3") (pintype "bidirectional"))
    )
    (net (code "6") (name "/3V3") (class "Default")
      (node (ref "U$9") (pin "17") (pinfunction "3V3_17") (pintype "power_in"))
    )
    (net (code "7") (name "/3V3_EN") (class "Default")
      (node (ref "IC6") (pin "5") (pinfunction "EN_5") (pintype "bidirectional"))
      (node (ref "U$10") (pin "8") (pinfunction "PA2_8") (pintype "bidirectional"))
    )
    (net (code "8") (name "/3V_STB") (class "Default")
      (node (ref "C7") (pin "1") (pinfunction "1_1") (pintype "passive"))
      (node (ref "IC2") (pin "2") (pinfunction "OUT_2") (pintype "output"))
      (node (ref "IC9") (pin "5") (pinfunction "VDD_5") (pintype "power_in"))
      (node (ref "JP5") (pin "4") (pinfunction "4_4") (pintype "passive"))
      (node (ref "R41") (pin "2") (pinfunction "2_2") (pintype "passive"))
      (node (ref "R42") (pin "2") (pinfunction "2_2") (pintype "passive"))
      (node (ref "U$10") (pin "16") (pinfunction "VDD_16") (pintype "bidirectional"))
      (node (ref "U$10") (pin "5") (pinfunction "VDDA_5") (pintype "bidirectional"))
    )
    (net (code "9") (name "/5V0@2") (class "Default")
      (node (ref "JP4") (pin "3") (pinfunction "3_3") (pintype "passive"))
      (node (ref "R43") (pin "2") (pinfunction "2_2") (pintype "passive"))
      (node (ref "U$9") (pin "2") (pinfunction "5V0_2") (pintype "power_in"))
      (node (ref "U$9") (pin "4") (pinfunction "5V0_4") (pintype "power_in"))
    )
    (net (code "10") (name "/5VM_EN") (class "Default")
      (node (ref "IC4") (pin "5") (pinfunction "EN_5") (pintype "bidirectional"))
      (node (ref "U$10") (pin "6") (pinfunction "PA0_6") (pintype "bidirectional"))
    )
    (net (code "11") (name "/5VU_EN") (class "Default")
      (node (ref "IC5") (pin "5") (pinfunction "EN_5") (pintype "bidirectional"))
      (node (ref "U$10") (pin "7") (pinfunction "PA1_7") (pintype "bidirectional"))
    )
    (net (code "12") (name "/ADC1") (class "Default")
      (node (ref "IC9") (pin "1") (pinfunction "VYSTUP_1") (pintype "output"))
      (node (ref "IC9") (pin "4") (pinfunction "IN-_4") (pintype "input"))
      (node (ref "U$10") (pin "11") (pinfunction "PA5_11") (pintype "bidirectional"))
    )
    (net (code "13") (name "/ADC2") (class "Default")
      (node (ref "R38") (pin "1") (pinfunction "1_1") (pintype "passive"))
      (node (ref "R39") (pin "2") (pinfunction "2_2") (pintype "passive"))
      (node (ref "U$10") (pin "14") (pinfunction "PB1_14") (pintype "bidirectional"))
    )
    (net (code "14") (name "/BKLT") (class "Default")
      (node (ref "JP4") (pin "4") (pinfunction "4_4") (pintype "passive"))
      (node (ref "U$9") (pin "13") (pinfunction "GPIO27/GEN2_13") (pintype "bidirectional"))
    )
    (net (code "15") (name "/BSTAT") (class "Default")
      (node (ref "R5") (pin "2") (pinfunction "2_2") (pintype "passive"))
      (node (ref "U$10") (pin "2") (pinfunction "PF0/OSCIN_2") (pintype "bidirectional"))
    )
    (net (code "16") (name "/CS") (class "Default")
      (node (ref "JP4") (pin "7") (pinfunction "7_7") (pintype "passive"))
      (node (ref "U$9") (pin "24") (pinfunction "~{CE0}/GPIO8_24") (pintype "bidirectional"))
    )
    (net (code "17") (name "/D+") (class "Default")
      (node (ref "D+") (pin "TP") (pinfunction "TP_TP") (pintype "input"))
      (node (ref "USB") (pin "16") (pinfunction "DPU_16") (pintype "bidirectional"))
    )
    (net (code "18") (name "/D-") (class "Default")
      (node (ref "D-") (pin "TP") (pinfunction "TP_TP") (pintype "input"))
      (node (ref "USB") (pin "15") (pinfunction "DMU_15") (pintype "bidirectional"))
    )
    (net (code "19") (name "/D{slash}C") (class "Default")
      (node (ref "JP4") (pin "8") (pinfunction "8_8") (pintype "passive"))
      (node (ref "U$9") (pin "18") (pinfunction "GEN5/GPIO24_18") (pintype "bidirectional"))
    )
    (net (code "20") (name "/JX") (class "Default")
      (node (ref "U$2") (pin "18") (pinfunction "PB0/ADC_IN8/TIM3_CH3_18") (pintype "bidirectional"))
      (node (ref "X") (pin "TP") (pinfunction "TP_TP") (pintype "input"))
    )
    (net (code "21") (name "/JY") (class "Default")
      (node (ref "U$2") (pin "19") (pinfunction "PB1/ADC_IN9/TIM3_CH4_19") (pintype "bidirectional"))
      (node (ref "Y") (pin "TP") (pinfunction "TP_TP") (pintype "input"))
    )
    (net (code "22") (name "/KC1") (class "Default")
      (node (ref "JP3") (pin "8") (pinfunction "8_8") (pintype "passive"))
      (node (ref "R12") (pin "1") (pinfunction "1_1") (pintype "passive"))
      (node (ref "U$2") (pin "40") (pinfunction "PB4/SPI1_MISO/TIM3_CH1_40") (pintype "bidirectional"))
      (node (ref "U$7") (pin "1") (pinfunction "C1_1") (pintype "bidirectional"))
    )
    (net (code "23") (name "/KC2") (class "Default")
      (node (ref "JP3") (pin "7") (pinfunction "7_7") (pintype "passive"))
      (node (ref "R13") (pin "1") (pinfunction "1_1") (pintype "passive"))
      (node (ref "U$2") (pin "41") (pinfunction "PB5/WKUP6/SPI1_MOSI/TIM3_CH2_41") (pintype "bidirectional"))
      (node (ref "U$7") (pin "2") (pinfunction "C2_2") (pintype "bidirectional"))
    )
    (net (code "24") (name "/KC3") (class "Default")
      (node (ref "JP3") (pin "6") (pinfunction "6_6") (pintype "passive"))
      (node (ref "R14") (pin "1") (pinfunction "1_1") (pintype "passive"))
      (node (ref "U$2") (pin "42") (pinfunction "PB6USART1_TX/I2C1_SCL_42") (pintype "bidirectional"))
      (node (ref "U$7") (pin "3") (pinfunction "C3_3") (pintype "bidirectional"))
    )
    (net (code "25") (name "/KC4") (class "Default")
      (node (ref "JP3") (pin "5") (pinfunction "5_5") (pintype "passive"))
      (node (ref "R15") (pin "1") (pinfunction "1_1") (pintype "passive"))
      (node (ref "U$2") (pin "45") (pinfunction "PB8/I2C1_SCL/TIM16_CH1/CAN_RX_45") (pintype "bidirectional"))
      (node (ref "U$7") (pin "4") (pinfunction "C4_4") (pintype "bidirectional"))
    )
    (net (code "26") (name "/KEYB_DM") (class "Default")
      (node (ref "U$2") (pin "32") (pinfunction "PA11/USB_DM/CAN_RX_32") (pintype "bidirectional"))
      (node (ref "USB") (pin "4") (pinfunction "DM4_4") (pintype "bidirectional"))
    )
    (net (code "27") (name "/KEYB_DP") (class "Default")
      (node (ref "U$2") (pin "33") (pinfunction "PA12/USB_DP/CAN_TX_33") (pintype "bidirectional"))
      (node (ref "USB") (pin "5") (pinfunction "DP4_5") (pintype "bidirectional"))
    )
    (net (code "28") (name "/KL1") (class "Default")
      (node (ref "LED1") (pin "A") (pinfunction "A_A") (pintype "passive"))
      (node (ref "U$2") (pin "13") (pinfunction "PA3/ADC_IN3/COMP2_INP/USART2_RX_13") (pintype "bidirectional"))
    )
    (net (code "29") (name "/KL2") (class "Default")
      (node (ref "LED2") (pin "A") (pinfunction "A_A") (pintype "passive"))
      (node (ref "U$2") (pin "14") (pinfunction "PA4/ADC_IN4/DAC_OUT1_14") (pintype "bidirectional"))
    )
    (net (code "30") (name "/KR1") (class "Default")
      (node (ref "JP3") (pin "4") (pinfunction "4_4") (pintype "passive"))
      (node (ref "U$2") (pin "46") (pinfunction "PB9/I2C1_SDA/TIM17_CH1/CAN_TX_46") (pintype "bidirectional"))
      (node (ref "U$7") (pin "5") (pinfunction "R1_5") (pintype "bidirectional"))
    )
    (net (code "31") (name "/KR2") (class "Default")
      (node (ref "JP3") (pin "3") (pinfunction "3_3") (pintype "passive"))
      (node (ref "U$2") (pin "2") (pinfunction "PC13/WKUP2/RTC_TAMP1/RTC_TS/RTC_OUT_2") (pintype "bidirectional"))
      (node (ref "U$7") (pin "6") (pinfunction "R2_6") (pintype "bidirectional"))
    )
    (net (code "32") (name "/KR3") (class "Default")
      (node (ref "JP3") (pin "2") (pinfunction "2_2") (pintype "passive"))
      (node (ref "U$2") (pin "3") (pinfunction "PC14/OSC32_IN_3") (pintype "bidirectional"))
      (node (ref "U$7") (pin "7") (pinfunction "R3_7") (pintype "bidirectional"))
    )
    (net (code "33") (name "/KR4") (class "Default")
      (node (ref "JP3") (pin "1") (pinfunction "1_1") (pintype "passive"))
      (node (ref "U$2") (pin "4") (pinfunction "PC15/OSC32_OUT_4") (pintype "bidirectional"))
      (node (ref "U$7") (pin "8") (pinfunction "R4_8") (pintype "bidirectional"))
    )
    (net (code "34") (name "/MK1") (class "Default")
      (node (ref "K2") (pin "1A") (pinfunction "1A_1A") (pintype "bidirectional"))
      (node (ref "U$2") (pin "10") (pinfunction "PA0/USART4_TX/WKUP1/ADC_IN0_10") (pintype "bidirectional"))
    )
    (net (code "35") (name "/MK2") (class "Default")
      (node (ref "K3") (pin "1B") (pinfunction "1B_1B") (pintype "bidirectional"))
      (node (ref "U$2") (pin "11") (pinfunction "PA1/ADC_IN1/COMP1_INP/USART4_RX_11") (pintype "bidirectional"))
    )
    (net (code "36") (name "/MK3") (class "Default")
      (node (ref "K1") (pin "1A") (pinfunction "1A_1A") (pintype "bidirectional"))
      (node (ref "R16") (pin "2") (pinfunction "2_2") (pintype "passive"))
      (node (ref "U$2") (pin "12") (pinfunction "PA2/ADC_IN2/WKUP4USART2_TX_12") (pintype "bidirectional"))
    )
    (net (code "37") (name "/PWM0") (class "Default")
      (node (ref "R47") (pin "2") (pinfunction "2_2") (pintype "passive"))
      (node (ref "U$9") (pin "12") (pinfunction "GPIO18_12") (pintype "bidirectional"))
    )
    (net (code "38") (name "/PWM1") (class "Default")
      (node (ref "R46") (pin "2") (pinfunction "2_2") (pintype "passive"))
      (node (ref "U$9") (pin "33") (pinfunction "GPIO13_33") (pintype "bidirectional"))
    )
    (net (code "39") (name "/RPG1") (class "Default")
      (node (ref "R28") (pin "1") (pinfunction "1_1") (pintype "passive"))
      (node (ref "U$9") (pin "35") (pinfunction "GPIO19_35") (pintype "bidirectional"))
    )
    (net (code "40") (name "/RPG2") (class "Default")
      (node (ref "R29") (pin "1") (pinfunction "1_1") (pintype "passive"))
      (node (ref "U$9") (pin "37") (pinfunction "GPIO26_37") (pintype "bidirectional"))
    )
    (net (code "41") (name "/RPRX") (class "Default")
      (node (ref "R30") (pin "1") (pinfunction "1_1") (pintype "passive"))
      (node (ref "U$9") (pin "10") (pinfunction "RXD0/GPIO15_10") (pintype "bidirectional"))
    )
    (net (code "42") (name "/RPTX") (class "Default")
      (node (ref "R31") (pin "1") (pinfunction "1_1") (pintype "passive"))
      (node (ref "U$9") (pin "8") (pinfunction "TXD0/GPIO14_8") (pintype "bidirectional"))
    )
    (net (code "43") (name "/RST") (class "Default")
      (node (ref "JP4") (pin "9") (pinfunction "9_9") (pintype "passive"))
      (node (ref "U$9") (pin "22") (pinfunction "GEN/6GPIO25_22") (pintype "bidirectional"))
    )
    (net (code "44") (name "/R_SCL") (class "Default")
      (node (ref "IC8") (pin "6") (pinfunction "SCL_6") (pintype "bidirectional"))
      (node (ref "R10") (pin "1") (pinfunction "1_1") (pintype "passive"))
      (node (ref "U$9") (pin "5") (pinfunction "GPIO3/SCL1_5") (pintype "bidirectional"))
    )
    (net (code "45") (name "/R_SDA") (class "Default")
      (node (ref "IC8") (pin "5") (pinfunction "SDA_5") (pintype "bidirectional"))
      (node (ref "R11") (pin "1") (pinfunction "1_1") (pintype "passive"))
      (node (ref "U$9") (pin "3") (pinfunction "GPIO2/SDA1_3") (pintype "bidirectional"))
    )
    (net (code "46") (name "/SCK") (class "Default")
      (node (ref "JP4") (pin "5") (pinfunction "5_5") (pintype "passive"))
      (node (ref "R37") (pin "1") (pinfunction "1_1") (pintype "passive"))
    )
    (net (code "47") (name "/SCK_R") (class "Default")
      (node (ref "R37") (pin "2") (pinfunction "2_2") (pintype "passive"))
      (node (ref "U$9") (pin "23") (pinfunction "GPIO11/SCLK_23") (pintype "bidirectional"))
    )
    (net (code "48") (name "/SDA") (class "Default")
      (node (ref "JP4") (pin "6") (pinfunction "6_6") (pintype "passive"))
      (node (ref "U$9") (pin "19") (pinfunction "GPIO10/MOSI_19") (pintype "bidirectional"))
    )
    (net (code "49") (name "/V25A") (class "Default")
      (node (ref "C42") (pin "2") (pinfunction "2_2") (pintype "passive"))
      (node (ref "IC10") (pin "5") (pinfunction "VDD_5") (pintype "bidirectional"))
      (node (ref "IC11") (pin "2") (pinfunction "OUT_2") (pintype "output"))
    )
    (net (code "50") (name "/V50A") (class "Default")
      (node (ref "C40") (pin "2") (pinfunction "2_2") (pintype "passive"))
      (node (ref "C44") (pin "+") (pinfunction "+_+") (pintype "passive"))
      (node (ref "IC11") (pin "3") (pinfunction "IN_3") (pintype "input"))
      (node (ref "R44") (pin "2") (pinfunction "2_2") (pintype "passive"))
      (node (ref "R53") (pin "2") (pinfunction "2_2") (pintype "passive"))
      (node (ref "U$11") (pin "8") (pinfunction "VDD_8") (pintype "bidirectional"))
    )
    (net (code "51") (name "/WL_D+") (class "Default")
      (node (ref "MOD1") (pin "D+") (pinfunction "D+_D+") (pintype "bidirectional"))
      (node (ref "USB") (pin "7") (pinfunction "DP3_7") (pintype "bidirectional"))
    )
    (net (code "52") (name "/WL_D-") (class "Default")
      (node (ref "MOD1") (pin "D-") (pinfunction "D-_D-") (pintype "bidirectional"))
      (node (ref "USB") (pin "6") (pinfunction "DM3_6") (pintype "bidirectional"))
    )
    (net (code "53") (name "GND") (class "Default")
      (node (ref "C1") (pin "1") (pinfunction "1_1") (pintype "passive"))
      (node (ref "C10") (pin "2") (pinfunction "2_2") (pintype "passive"))
      (node (ref "C11") (pin "2") (pinfunction "2_2") (pintype "passive"))
      (node (ref "C12") (pin "2") (pinfunction "2_2") (pintype "passive"))
      (node (ref "C13") (pin "2") (pinfunction "2_2") (pintype "passive"))
      (node (ref "C14") (pin "2") (pinfunction "2_2") (pintype "passive"))
      (node (ref "C15") (pin "2") (pinfunction "2_2") (pintype "passive"))
      (node (ref "C16") (pin "2") (pinfunction "2_2") (pintype "passive"))
      (node (ref "C2") (pin "1") (pinfunction "1_1") (pintype "passive"))
      (node (ref "C20") (pin "2") (pinfunction "2_2") (pintype "passive"))
      (node (ref "C21") (pin "2") (pinfunction "2_2") (pintype "passive"))
      (node (ref "C22") (pin "2") (pinfunction "2_2") (pintype "passive"))
      (node (ref "C23") (pin "2") (pinfunction "2_2") (pintype "passive"))
      (node (ref "C24") (pin "2") (pinfunction "2_2") (pintype "passive"))
      (node (ref "C25") (pin "2") (pinfunction "2_2") (pintype "passive"))
      (node (ref "C26") (pin "2") (pinfunction "2_2") (pintype "passive"))
      (node (ref "C27") (pin "2") (pinfunction "2_2") (pintype "passive"))
      (node (ref "C28") (pin "2") (pinfunction "2_2") (pintype "passive"))
      (node (ref "C29") (pin "2") (pinfunction "2_2") (pintype "passive"))
      (node (ref "C3") (pin "2") (pinfunction "2_2") (pintype "passive"))
      (node (ref "C30") (pin "1") (pinfunction "1_1") (pintype "passive"))
      (node (ref "C31") (pin "1") (pinfunction "1_1") (pintype "passive"))
      (node (ref "C32") (pin "-") (pinfunction "-_-") (pintype "passive"))
      (node (ref "C33") (pin "1") (pinfunction "1_1") (pintype "passive"))
      (node (ref "C34") (pin "1") (pinfunction "1_1") (pintype "passive"))
      (node (ref "C35") (pin "1") (pinfunction "1_1") (pintype "passive"))
      (node (ref "C37") (pin "1") (pinfunction "1_1") (pintype "passive"))
      (node (ref "C38") (pin "1") (pinfunction "1_1") (pintype "passive"))
      (node (ref "C4") (pin "2") (pinfunction "2_2") (pintype "passive"))
      (node (ref "C40") (pin "1") (pinfunction "1_1") (pintype "passive"))
      (node (ref "C41") (pin "1") (pinfunction "1_1") (pintype "passive"))
      (node (ref "C42") (pin "1") (pinfunction "1_1") (pintype "passive"))
      (node (ref "C43") (pin "1") (pinfunction "1_1") (pintype "passive"))
      (node (ref "C44") (pin "-") (pinfunction "-_-") (pintype "passive"))
      (node (ref "C45") (pin "-") (pinfunction "-_-") (pintype "passive"))
      (node (ref "C46") (pin "-") (pinfunction "-_-") (pintype "passive"))
      (node (ref "C5") (pin "2") (pinfunction "2_2") (pintype "passive"))
      (node (ref "C6") (pin "2") (pinfunction "2_2") (pintype "passive"))
      (node (ref "C7") (pin "2") (pinfunction "2_2") (pintype "passive"))
      (node (ref "C8") (pin "2") (pinfunction "2_2") (pintype "passive"))
      (node (ref "C9") (pin "2") (pinfunction "2_2") (pintype "passive"))
      (node (ref "D1") (pin "A") (pinfunction "A_A") (pintype "passive"))
      (node (ref "GND") (pin "TP") (pinfunction "TP_TP") (pintype "input"))
      (node (ref "IC1") (pin "6") (pinfunction "GND_6") (pintype "bidirectional"))
      (node (ref "IC10") (pin "2") (pinfunction "GND_2") (pintype "bidirectional"))
      (node (ref "IC11") (pin "1") (pinfunction "VSS_1") (pintype "input"))
      (node (ref "IC2") (pin "1") (pinfunction "VSS_1") (pintype "input"))
      (node (ref "IC3") (pin "1") (pinfunction "VSS_1") (pintype "input"))
      (node (ref "IC4") (pin "1") (pinfunction "GND_1") (pintype "bidirectional"))
      (node (ref "IC5") (pin "1") (pinfunction "GND_1") (pintype "bidirectional"))
      (node (ref "IC6") (pin "1") (pinfunction "GND_1") (pintype "bidirectional"))
      (node (ref "IC7") (pin "3") (pinfunction "~{WP}_3") (pintype "input"))
      (node (ref "IC7") (pin "4") (pinfunction "VSS_4") (pintype "power_in"))
      (node (ref "IC7") (pin "7") (pinfunction "~{HOLD}_7") (pintype "input"))
      (node (ref "IC8") (pin "4") (pinfunction "VSS_4") (pintype "bidirectional"))
      (node (ref "IC9") (pin "2") (pinfunction "VSS_2") (pintype "power_in"))
      (node (ref "JP1") (pin "2") (pinfunction "2_2") (pintype "passive"))
      (node (ref "JP2") (pin "5") (pinfunction "5_5") (pintype "passive"))
      (node (ref "JP4") (pin "1") (pinfunction "1_1") (pintype "passive"))
      (node (ref "JP5") (pin "5") (pinfunction "5_5") (pintype "passive"))
      (node (ref "JP7") (pin "SLEEVE") (pinfunction "SLEEVE_SLEEVE") (pintype "bidirectional"))
      (node (ref "K1") (pin "1B") (pinfunction "1B_1B") (pintype "bidirectional"))
      (node (ref "K2") (pin "2B") (pinfunction "2B_2B") (pintype "bidirectional"))
      (node (ref "K3") (pin "2A") (pinfunction "2A_2A") (pintype "bidirectional"))
      (node (ref "K4") (pin "2B") (pinfunction "2B_2B") (pintype "bidirectional"))
      (node (ref "MOD1") (pin "GND") (pinfunction "GND_GND") (pintype "bidirectional"))
      (node (ref "MOD1") (pin "RFGND") (pinfunction "RFGND_RFGND") (pintype "bidirectional"))
      (node (ref "R19") (pin "1") (pinfunction "1_1") (pintype "passive"))
      (node (ref "R2") (pin "2") (pinfunction "2_2") (pintype "passive"))
      (node (ref "R20") (pin "1") (pinfunction "1_1") (pintype "passive"))
      (node (ref "R21") (pin "1") (pinfunction "1_1") (pintype "passive"))
      (node (ref "R23") (pin "1") (pinfunction "1_1") (pintype "passive"))
      (node (ref "R25") (pin "1") (pinfunction "1_1") (pintype "passive"))
      (node (ref "R27") (pin "1") (pinfunction "1_1") (pintype "passive"))
      (node (ref "R32") (pin "1") (pinfunction "1_1") (pintype "passive"))
      (node (ref "R33") (pin "1") (pinfunction "1_1") (pintype "passive"))
      (node (ref "R35") (pin "1") (pinfunction "1_1") (pintype "passive"))
      (node (ref "R39") (pin "1") (pinfunction "1_1") (pintype "passive"))
      (node (ref "R40") (pin "2") (pinfunction "2_2") (pintype "passive"))
      (node (ref "R45") (pin "1") (pinfunction "1_1") (pintype "passive"))
      (node (ref "R48") (pin "1") (pinfunction "1_1") (pintype "passive"))
      (node (ref "R49") (pin "1") (pinfunction "1_1") (pintype "passive"))
      (node (ref "R50") (pin "1") (pinfunction "1_1") (pintype "passive"))
      (node (ref "R63") (pin "2") (pinfunction "2_2") (pintype "passive"))
      (node (ref "R64") (pin "2") (pinfunction "2_2") (pintype "passive"))
      (node (ref "R8") (pin "1") (pinfunction "1_1") (pintype "passive"))
      (node (ref "TP1") (pin "TP") (pinfunction "TP_TP") (pintype "input"))
      (node (ref "TP2") (pin "TP") (pinfunction "TP_TP") (pintype "input"))
      (node (ref "U$1") (pin "2") (pinfunction "N_2") (pintype "bidirectional"))
      (node (ref "U$1") (pin "3") (pinfunction "SW_3") (pintype "bidirectional"))
      (node (ref "U$10") (pin "15") (pinfunction "VSS_15") (pintype "bidirectional"))
      (node (ref "U$11") (pin "4") (pinfunction "GND_4") (pintype "bidirectional"))
      (node (ref "U$12") (pin "G") (pinfunction "G_G") (pintype "bidirectional"))
      (node (ref "U$2") (pin "23") (pinfunction "VSS_1(P23)_23") (pintype "bidirectional"))
      (node (ref "U$2") (pin "35") (pinfunction "VSS_2(P35)_35") (pintype "bidirectional"))
      (node (ref "U$2") (pin "47") (pinfunction "VSS_3(P47)_47") (pintype "bidirectional"))
      (node (ref "U$2") (pin "8") (pinfunction "VSSA(P8)_8") (pintype "bidirectional"))
      (node (ref "U$9") (pin "14") (pinfunction "GND_14") (pintype "power_in"))
      (node (ref "U$9") (pin "20") (pinfunction "GND_20") (pintype "power_in"))
      (node (ref "U$9") (pin "25") (pinfunction "GND_25") (pintype "power_in"))
      (node (ref "U$9") (pin "30") (pinfunction "GND_30") (pintype "power_in"))
      (node (ref "U$9") (pin "34") (pinfunction "GND_34") (pintype "power_in"))
      (node (ref "U$9") (pin "39") (pinfunction "GND_39") (pintype "power_in"))
      (node (ref "U$9") (pin "9") (pinfunction "GND_9") (pintype "power_in"))
      (node (ref "USB") (pin "1") (pinfunction "VSS_1") (pintype "bidirectional"))
      (node (ref "USB1") (pin "GND") (pinfunction "GND_GND") (pintype "bidirectional"))
      (node (ref "USB1") (pin "GND@1") (pinfunction "GND_GND@1") (pintype "bidirectional"))
      (node (ref "USB1") (pin "GND@2") (pinfunction "GND_GND@2") (pintype "bidirectional"))
      (node (ref "USB2") (pin "GND") (pinfunction "GND_GND") (pintype "bidirectional"))
      (node (ref "USB2") (pin "GND@1") (pinfunction "GND_GND@1") (pintype "bidirectional"))
      (node (ref "USB2") (pin "GND@2") (pinfunction "GND_GND@2") (pintype "bidirectional"))
    )
    (net (code "54") (name "Net-(ANT1-P$1)") (class "Default")
      (node (ref "ANT1") (pin "1") (pinfunction "P$1_1") (pintype "bidirectional"))
      (node (ref "MOD1") (pin "ANT") (pinfunction "ANT_ANT") (pintype "bidirectional"))
    )
    (net (code "55") (name "Net-(C30-Pad2)") (class "Default")
      (node (ref "C30") (pin "2") (pinfunction "2_2") (pintype "passive"))
      (node (ref "MOD1") (pin "3V3") (pinfunction "3V3_3V3") (pintype "bidirectional"))
      (node (ref "R36") (pin "2") (pinfunction "2_2") (pintype "passive"))
    )
    (net (code "56") (name "Net-(C36-Pad+)") (class "Default")
      (node (ref "C36") (pin "+") (pinfunction "+_+") (pintype "passive"))
      (node (ref "R55") (pin "1") (pinfunction "1_1") (pintype "passive"))
    )
    (net (code "57") (name "Net-(C36-Pad-)") (class "Default")
      (node (ref "C36") (pin "-") (pinfunction "-_-") (pintype "passive"))
      (node (ref "U$12") (pin "W2") (pinfunction "W2_W2") (pintype "bidirectional"))
    )
    (net (code "58") (name "Net-(C38-Pad2)") (class "Default")
      (node (ref "C38") (pin "2") (pinfunction "2_2") (pintype "passive"))
      (node (ref "R52") (pin "1") (pinfunction "1_1") (pintype "passive"))
      (node (ref "R53") (pin "1") (pinfunction "1_1") (pintype "passive"))
    )
    (net (code "59") (name "Net-(C39-Pad+)") (class "Default")
      (node (ref "C39") (pin "+") (pinfunction "+_+") (pintype "passive"))
      (node (ref "R54") (pin "1") (pinfunction "1_1") (pintype "passive"))
    )
    (net (code "60") (name "Net-(C39-Pad-)") (class "Default")
      (node (ref "C39") (pin "-") (pinfunction "-_-") (pintype "passive"))
      (node (ref "U$12") (pin "W1") (pinfunction "W1_W1") (pintype "bidirectional"))
    )
    (net (code "61") (name "Net-(C41-Pad2)") (class "Default")
      (node (ref "C41") (pin "2") (pinfunction "2_2") (pintype "passive"))
      (node (ref "R57") (pin "1") (pinfunction "1_1") (pintype "passive"))
      (node (ref "R63") (pin "1") (pinfunction "1_1") (pintype "passive"))
      (node (ref "U$12") (pin "T1") (pinfunction "T1_T1") (pintype "bidirectional"))
    )
    (net (code "62") (name "Net-(C43-Pad2)") (class "Default")
      (node (ref "C43") (pin "2") (pinfunction "2_2") (pintype "passive"))
      (node (ref "R56") (pin "1") (pinfunction "1_1") (pintype "passive"))
      (node (ref "R64") (pin "1") (pinfunction "1_1") (pintype "passive"))
      (node (ref "U$12") (pin "T2") (pinfunction "T2_T2") (pintype "bidirectional"))
    )
    (net (code "63") (name "Net-(C45-Pad+)") (class "Default")
      (node (ref "C45") (pin "+") (pinfunction "+_+") (pintype "passive"))
      (node (ref "C46") (pin "+") (pinfunction "+_+") (pintype "passive"))
      (node (ref "R65") (pin "1") (pinfunction "1_1") (pintype "passive"))
      (node (ref "USB1") (pin "VBUS") (pinfunction "VBUS_VBUS") (pintype "bidirectional"))
      (node (ref "USB2") (pin "VBUS") (pinfunction "VBUS_VBUS") (pintype "bidirectional"))
    )
    (net (code "64") (name "Net-(IC1-DRV)") (class "Default")
      (node (ref "IC1") (pin "8") (pinfunction "DRV_8") (pintype "bidirectional"))
      (node (ref "T2") (pin "4") (pinfunction "G_4") (pintype "bidirectional"))
    )
    (net (code "65") (name "Net-(IC1-EN)") (class "Default")
      (node (ref "IC1") (pin "4") (pinfunction "EN_4") (pintype "bidirectional"))
      (node (ref "R3") (pin "2") (pinfunction "2_2") (pintype "passive"))
    )
    (net (code "66") (name "Net-(IC1-SEN)") (class "Default")
      (node (ref "IC1") (pin "1") (pinfunction "SEN_1") (pintype "bidirectional"))
      (node (ref "R4") (pin "2") (pinfunction "2_2") (pintype "passive"))
      (node (ref "T2") (pin "1") (pinfunction "S_1") (pintype "bidirectional"))
      (node (ref "T2") (pin "2") (pinfunction "S_2") (pintype "bidirectional"))
      (node (ref "T2") (pin "3") (pinfunction "S_3") (pintype "bidirectional"))
    )
    (net (code "67") (name "Net-(IC1-STAT)") (class "Default")
      (node (ref "IC1") (pin "3") (pinfunction "STAT_3") (pintype "bidirectional"))
      (node (ref "R5") (pin "1") (pinfunction "1_1") (pintype "passive"))
    )
    (net (code "68") (name "Net-(IC1-TMR)") (class "Default")
      (node (ref "C5") (pin "1") (pinfunction "1_1") (pintype "passive"))
      (node (ref "IC1") (pin "5") (pinfunction "TMR_5") (pintype "bidirectional"))
    )
    (net (code "69") (name "Net-(IC1-VBAT)") (class "Default")
      (node (ref "IC1") (pin "7") (pinfunction "VBAT_7") (pintype "bidirectional"))
      (node (ref "PTC2") (pin "P$2") (pinfunction "2_P$2") (pintype "passive"))
      (node (ref "T2") (pin "5") (pinfunction "D_5") (pintype "bidirectional"))
      (node (ref "T2") (pin "6") (pinfunction "D_6") (pintype "bidirectional"))
      (node (ref "T2") (pin "7") (pinfunction "D_7") (pintype "bidirectional"))
      (node (ref "T2") (pin "8") (pinfunction "D_8") (pintype "bidirectional"))
      (node (ref "T3") (pin "5") (pinfunction "D_5") (pintype "bidirectional"))
      (node (ref "T3") (pin "6") (pinfunction "D_6") (pintype "bidirectional"))
      (node (ref "T3") (pin "7") (pinfunction "D_7") (pintype "bidirectional"))
      (node (ref "T3") (pin "8") (pinfunction "D_8") (pintype "bidirectional"))
    )
    (net (code "70") (name "Net-(IC2-IN)") (class "Default")
      (node (ref "C3") (pin "1") (pinfunction "1_1") (pintype "passive"))
      (node (ref "IC2") (pin "3") (pinfunction "IN_3") (pintype "input"))
      (node (ref "R6") (pin "1") (pinfunction "1_1") (pintype "passive"))
    )
    (net (code "71") (name "Net-(IC3-IN)") (class "Default")
      (node (ref "C4") (pin "1") (pinfunction "1_1") (pintype "passive"))
      (node (ref "IC3") (pin "3") (pinfunction "IN_3") (pintype "input"))
      (node (ref "R7") (pin "2") (pinfunction "2_2") (pintype "passive"))
    )
    (net (code "72") (name "Net-(IC4-SW)") (class "Default")
      (node (ref "C17") (pin "2") (pinfunction "2_2") (pintype "passive"))
      (node (ref "IC4") (pin "2") (pinfunction "SW_2") (pintype "bidirectional"))
      (node (ref "U$3") (pin "P$1") (pinfunction "P$1_P$1") (pintype "bidirectional"))
    )
    (net (code "73") (name "Net-(IC4-VBST)") (class "Default")
      (node (ref "C17") (pin "1") (pinfunction "1_1") (pintype "passive"))
      (node (ref "IC4") (pin "6") (pinfunction "VBST_6") (pintype "bidirectional"))
    )
    (net (code "74") (name "Net-(IC4-VFB)") (class "Default")
      (node (ref "IC4") (pin "4") (pinfunction "VFB_4") (pintype "bidirectional"))
      (node (ref "R22") (pin "2") (pinfunction "2_2") (pintype "passive"))
      (node (ref "R23") (pin "2") (pinfunction "2_2") (pintype "passive"))
    )
    (net (code "75") (name "Net-(IC5-SW)") (class "Default")
      (node (ref "C18") (pin "2") (pinfunction "2_2") (pintype "passive"))
      (node (ref "IC5") (pin "2") (pinfunction "SW_2") (pintype "bidirectional"))
      (node (ref "U$4") (pin "P$1") (pinfunction "P$1_P$1") (pintype "bidirectional"))
    )
    (net (code "76") (name "Net-(IC5-VBST)") (class "Default")
      (node (ref "C18") (pin "1") (pinfunction "1_1") (pintype "passive"))
      (node (ref "IC5") (pin "6") (pinfunction "VBST_6") (pintype "bidirectional"))
    )
    (net (code "77") (name "Net-(IC5-VFB)") (class "Default")
      (node (ref "IC5") (pin "4") (pinfunction "VFB_4") (pintype "bidirectional"))
      (node (ref "R24") (pin "2") (pinfunction "2_2") (pintype "passive"))
      (node (ref "R25") (pin "2") (pinfunction "2_2") (pintype "passive"))
    )
    (net (code "78") (name "Net-(IC6-SW)") (class "Default")
      (node (ref "C19") (pin "2") (pinfunction "2_2") (pintype "passive"))
      (node (ref "IC6") (pin "2") (pinfunction "SW_2") (pintype "bidirectional"))
      (node (ref "U$5") (pin "P$1") (pinfunction "P$1_P$1") (pintype "bidirectional"))
    )
    (net (code "79") (name "Net-(IC6-VBST)") (class "Default")
      (node (ref "C19") (pin "1") (pinfunction "1_1") (pintype "passive"))
      (node (ref "IC6") (pin "6") (pinfunction "VBST_6") (pintype "bidirectional"))
    )
    (net (code "80") (name "Net-(IC6-VFB)") (class "Default")
      (node (ref "IC6") (pin "4") (pinfunction "VFB_4") (pintype "bidirectional"))
      (node (ref "R26") (pin "2") (pinfunction "2_2") (pintype "passive"))
      (node (ref "R27") (pin "2") (pinfunction "2_2") (pintype "passive"))
    )
    (net (code "81") (name "Net-(IC7-SCK)") (class "Default")
      (node (ref "IC7") (pin "6") (pinfunction "SCK_6") (pintype "input"))
      (node (ref "U$2") (pin "26") (pinfunction "PB13/SPI2_SCK/I2C2_SCL_26") (pintype "bidirectional"))
    )
    (net (code "82") (name "Net-(IC7-SI)") (class "Default")
      (node (ref "IC7") (pin "5") (pinfunction "SI_5") (pintype "input"))
      (node (ref "U$2") (pin "28") (pinfunction "PB15/WKUP7/RTC_REFIN/SPI2_MOSI_28") (pintype "bidirectional"))
    )
    (net (code "83") (name "Net-(IC7-SO)") (class "Default")
      (node (ref "IC7") (pin "2") (pinfunction "SO_2") (pintype "input"))
      (node (ref "U$2") (pin "27") (pinfunction "PB14/SPI2_MISO/I2C2_SDA_27") (pintype "bidirectional"))
    )
    (net (code "84") (name "Net-(IC7-~{CS})") (class "Default")
      (node (ref "IC7") (pin "1") (pinfunction "~{CS}_1") (pintype "input"))
      (node (ref "R9") (pin "2") (pinfunction "2_2") (pintype "passive"))
      (node (ref "U$2") (pin "29") (pinfunction "PA8/TIM1_CH1_29") (pintype "bidirectional"))
    )
    (net (code "85") (name "Net-(IC8-OSI)") (class "Default")
      (node (ref "IC8") (pin "1") (pinfunction "OSI_1") (pintype "bidirectional"))
      (node (ref "Q1") (pin "1") (pinfunction "1_1") (pintype "bidirectional"))
    )
    (net (code "86") (name "Net-(IC8-OSO)") (class "Default")
      (node (ref "IC8") (pin "2") (pinfunction "OSO_2") (pintype "bidirectional"))
      (node (ref "Q1") (pin "4") (pinfunction "2_4") (pintype "bidirectional"))
    )
    (net (code "87") (name "Net-(IC8-VBAT)") (class "Default")
      (node (ref "IC8") (pin "3") (pinfunction "VBAT_3") (pintype "bidirectional"))
      (node (ref "U$6") (pin "POS") (pinfunction "P_POS") (pintype "bidirectional"))
    )
    (net (code "88") (name "Net-(IC9A-NEIN+)") (class "Default")
      (node (ref "IC9") (pin "3") (pinfunction "NEIN+_3") (pintype "input"))
      (node (ref "R34") (pin "1") (pinfunction "1_1") (pintype "passive"))
      (node (ref "R35") (pin "2") (pinfunction "2_2") (pintype "passive"))
    )
    (net (code "89") (name "Net-(IC10-1A)") (class "Default")
      (node (ref "IC10") (pin "1") (pinfunction "1A_1") (pintype "bidirectional"))
      (node (ref "R46") (pin "1") (pinfunction "1_1") (pintype "passive"))
      (node (ref "R48") (pin "2") (pinfunction "2_2") (pintype "passive"))
    )
    (net (code "90") (name "Net-(IC10-1Y)") (class "Default")
      (node (ref "IC10") (pin "6") (pinfunction "1Y_6") (pintype "bidirectional"))
      (node (ref "R56") (pin "2") (pinfunction "2_2") (pintype "passive"))
    )
    (net (code "91") (name "Net-(IC10-2A)") (class "Default")
      (node (ref "IC10") (pin "3") (pinfunction "2A_3") (pintype "bidirectional"))
      (node (ref "R47") (pin "1") (pinfunction "1_1") (pintype "passive"))
      (node (ref "R49") (pin "2") (pinfunction "2_2") (pintype "passive"))
    )
    (net (code "92") (name "Net-(IC10-2Y)") (class "Default")
      (node (ref "IC10") (pin "4") (pinfunction "2Y_4") (pintype "bidirectional"))
      (node (ref "R57") (pin "2") (pinfunction "2_2") (pintype "passive"))
    )
    (net (code "93") (name "Net-(JP6-Pad3)") (class "Default")
      (node (ref "JP6") (pin "3") (pinfunction "3_3") (pintype "passive"))
      (node (ref "R58") (pin "2") (pinfunction "2_2") (pintype "passive"))
    )
    (net (code "94") (name "Net-(JP6-Pad4)") (class "Default")
      (node (ref "JP6") (pin "4") (pinfunction "4_4") (pintype "passive"))
      (node (ref "R59") (pin "1") (pinfunction "1_1") (pintype "passive"))
    )
    (net (code "95") (name "Net-(JP7-LEFT)") (class "Default")
      (node (ref "C47") (pin "-") (pinfunction "-_-") (pintype "passive"))
      (node (ref "JP7") (pin "TIP") (pinfunction "LEFT_TIP") (pintype "bidirectional"))
    )
    (net (code "96") (name "Net-(JP7-RIGHT)") (class "Default")
      (node (ref "C48") (pin "-") (pinfunction "-_-") (pintype "passive"))
      (node (ref "JP7") (pin "RING") (pinfunction "RIGHT_RING") (pintype "bidirectional"))
    )
    (net (code "97") (name "Net-(K2-Pad2A)") (class "Default")
      (node (ref "K2") (pin "2A") (pinfunction "2A_2A") (pintype "bidirectional"))
      (node (ref "R17") (pin "2") (pinfunction "2_2") (pintype "passive"))
    )
    (net (code "98") (name "Net-(K3-Pad2B)") (class "Default")
      (node (ref "K3") (pin "2B") (pinfunction "2B_2B") (pintype "bidirectional"))
      (node (ref "R18") (pin "2") (pinfunction "2_2") (pintype "passive"))
    )
    (net (code "99") (name "Net-(LED1-C)") (class "Default")
      (node (ref "LED1") (pin "K") (pinfunction "C_K") (pintype "passive"))
      (node (ref "R19") (pin "2") (pinfunction "2_2") (pintype "passive"))
    )
    (net (code "100") (name "Net-(LED2-C)") (class "Default")
      (node (ref "LED2") (pin "K") (pinfunction "C_K") (pintype "passive"))
      (node (ref "R20") (pin "2") (pinfunction "2_2") (pintype "passive"))
    )
    (net (code "101") (name "Net-(LED3-C)") (class "Default")
      (node (ref "LED3") (pin "K") (pinfunction "C_K") (pintype "passive"))
      (node (ref "R32") (pin "2") (pinfunction "2_2") (pintype "passive"))
    )
    (net (code "102") (name "Net-(LED4-C)") (class "Default")
      (node (ref "LED4") (pin "K") (pinfunction "C_K") (pintype "passive"))
      (node (ref "R33") (pin "2") (pinfunction "2_2") (pintype "passive"))
    )
    (net (code "103") (name "Net-(PTC1-1)") (class "Default")
      (node (ref "D1") (pin "C") (pinfunction "C_C") (pintype "passive"))
      (node (ref "D3") (pin "A") (pinfunction "A_A") (pintype "passive"))
      (node (ref "PTC1") (pin "P$1") (pinfunction "1_P$1") (pintype "passive"))
      (node (ref "T1") (pin "5") (pinfunction "D_5") (pintype "bidirectional"))
      (node (ref "T1") (pin "6") (pinfunction "D_6") (pintype "bidirectional"))
      (node (ref "T1") (pin "7") (pinfunction "D_7") (pintype "bidirectional"))
      (node (ref "T1") (pin "8") (pinfunction "D_8") (pintype "bidirectional"))
      (node (ref "T3") (pin "4") (pinfunction "G_4") (pintype "bidirectional"))
    )
    (net (code "104") (name "Net-(PTC1-2)") (class "Default")
      (node (ref "PTC1") (pin "P$2") (pinfunction "2_P$2") (pintype "passive"))
      (node (ref "U$1") (pin "1") (pinfunction "P_1") (pintype "bidirectional"))
    )
    (net (code "105") (name "Net-(PTC2-1)") (class "Default")
      (node (ref "JP1") (pin "1") (pinfunction "1_1") (pintype "passive"))
      (node (ref "PTC2") (pin "P$1") (pinfunction "1_P$1") (pintype "passive"))
    )
    (net (code "106") (name "Net-(T1-G)") (class "Default")
      (node (ref "D2") (pin "A") (pinfunction "A_A") (pintype "passive"))
      (node (ref "R8") (pin "2") (pinfunction "2_2") (pintype "passive"))
      (node (ref "T1") (pin "4") (pinfunction "G_4") (pintype "bidirectional"))
    )
    (net (code "107") (name "Net-(T4-B)") (class "Default")
      (node (ref "R59") (pin "2") (pinfunction "2_2") (pintype "passive"))
      (node (ref "R62") (pin "1") (pinfunction "1_1") (pintype "passive"))
      (node (ref "T4") (pin "1") (pinfunction "B_1") (pintype "passive"))
    )
    (net (code "108") (name "Net-(T4-C)") (class "Default")
      (node (ref "T4") (pin "3") (pinfunction "C_3") (pintype "passive"))
      (node (ref "TFT1") (pin "11") (pinfunction "LEDK1_11") (pintype "bidirectional"))
      (node (ref "TFT1") (pin "12") (pinfunction "LEDK2_12") (pintype "bidirectional"))
      (node (ref "TFT1") (pin "13") (pinfunction "LEDK3_13") (pintype "bidirectional"))
      (node (ref "TFT1") (pin "14") (pinfunction "LEDK4_14") (pintype "bidirectional"))
    )
    (net (code "109") (name "Net-(T4-E)") (class "Default")
      (node (ref "JP6") (pin "1") (pinfunction "1_1") (pintype "passive"))
      (node (ref "T4") (pin "2") (pinfunction "E_2") (pintype "passive"))
      (node (ref "TFT1") (pin "1") (pinfunction "GND1_1") (pintype "bidirectional"))
      (node (ref "TFT1") (pin "8") (pinfunction "GND2_8") (pintype "bidirectional"))
    )
    (net (code "110") (name "Net-(TFT1-CS)") (class "Default")
      (node (ref "JP6") (pin "7") (pinfunction "7_7") (pintype "passive"))
      (node (ref "TFT1") (pin "5") (pinfunction "CS_5") (pintype "bidirectional"))
    )
    (net (code "111") (name "Net-(TFT1-D{slash}C)") (class "Default")
      (node (ref "JP6") (pin "8") (pinfunction "8_8") (pintype "passive"))
      (node (ref "TFT1") (pin "4") (pinfunction "D/C_4") (pintype "bidirectional"))
    )
    (net (code "112") (name "Net-(TFT1-LEDA)") (class "Default")
      (node (ref "R58") (pin "1") (pinfunction "1_1") (pintype "passive"))
      (node (ref "TFT1") (pin "10") (pinfunction "LEDA_10") (pintype "bidirectional"))
    )
    (net (code "113") (name "Net-(TFT1-RST)") (class "Default")
      (node (ref "JP6") (pin "9") (pinfunction "9_9") (pintype "passive"))
      (node (ref "TFT1") (pin "2") (pinfunction "RST_2") (pintype "bidirectional"))
    )
    (net (code "114") (name "Net-(TFT1-SCK)") (class "Default")
      (node (ref "JP6") (pin "5") (pinfunction "5_5") (pintype "passive"))
      (node (ref "TFT1") (pin "3") (pinfunction "SCK_3") (pintype "bidirectional"))
    )
    (net (code "115") (name "Net-(TFT1-SDA)") (class "Default")
      (node (ref "JP6") (pin "6") (pinfunction "6_6") (pintype "passive"))
      (node (ref "TFT1") (pin "6") (pinfunction "SDA_6") (pintype "bidirectional"))
    )
    (net (code "116") (name "Net-(TFT1-VDD)") (class "Default")
      (node (ref "JP6") (pin "2") (pinfunction "2_2") (pintype "passive"))
      (node (ref "R62") (pin "2") (pinfunction "2_2") (pintype "passive"))
      (node (ref "TFT1") (pin "9") (pinfunction "VDD_9") (pintype "bidirectional"))
    )
    (net (code "117") (name "Net-(U$2-BOOT0(P44))") (class "Default")
      (node (ref "R2") (pin "1") (pinfunction "1_1") (pintype "passive"))
      (node (ref "U$2") (pin "44") (pinfunction "BOOT0(P44)_44") (pintype "bidirectional"))
    )
    (net (code "118") (name "Net-(U$2-NRST(P7))") (class "Default")
      (node (ref "JP2") (pin "2") (pinfunction "2_2") (pintype "passive"))
      (node (ref "R1") (pin "1") (pinfunction "1_1") (pintype "passive"))
      (node (ref "U$2") (pin "7") (pinfunction "NRST(P7)_7") (pintype "bidirectional"))
    )
    (net (code "119") (name "Net-(U$2-PA5{slash}ADC_IN5{slash}DAC_OUT2{slash}SPI1_SCK)") (class "Default")
      (node (ref "U$2") (pin "15") (pinfunction "PA5/ADC_IN5/DAC_OUT2/SPI1_SCK_15") (pintype "bidirectional"))
      (node (ref "X2") (pin "TP") (pinfunction "TP_TP") (pintype "input"))
    )
    (net (code "120") (name "Net-(U$2-PA6{slash}ADC_IN6{slash}SPI1_MISO{slash}TIM3_CH1)") (class "Default")
      (node (ref "U$2") (pin "16") (pinfunction "PA6/ADC_IN6/SPI1_MISO/TIM3_CH1_16") (pintype "bidirectional"))
      (node (ref "X3") (pin "TP") (pinfunction "TP_TP") (pintype "input"))
    )
    (net (code "121") (name "Net-(U$2-PA7{slash}ADC_IN7{slash}SPI1_MOSI{slash}TIM3_CH2)") (class "Default")
      (node (ref "U$2") (pin "17") (pinfunction "PA7/ADC_IN7/SPI1_MOSI/TIM3_CH2_17") (pintype "bidirectional"))
      (node (ref "X4") (pin "TP") (pinfunction "TP_TP") (pintype "input"))
    )
    (net (code "122") (name "Net-(U$2-PA9{slash}USART1_TX{slash}TIM1_CH2)") (class "Default")
      (node (ref "U$2") (pin "30") (pinfunction "PA9/USART1_TX/TIM1_CH2_30") (pintype "bidirectional"))
      (node (ref "X5") (pin "TP") (pinfunction "TP_TP") (pintype "input"))
    )
    (net (code "123") (name "Net-(U$2-PA10{slash}USART1_RX{slash}TIM1_CH3)") (class "Default")
      (node (ref "U$2") (pin "31") (pinfunction "PA10/USART1_RX/TIM1_CH3_31") (pintype "bidirectional"))
      (node (ref "X6") (pin "TP") (pinfunction "TP_TP") (pintype "input"))
    )
    (net (code "124") (name "Net-(U$2-PA13{slash}SWDIO)") (class "Default")
      (node (ref "JP2") (pin "1") (pinfunction "1_1") (pintype "passive"))
      (node (ref "U$2") (pin "34") (pinfunction "PA13/SWDIO_34") (pintype "bidirectional"))
    )
    (net (code "125") (name "Net-(U$2-PA14{slash}USART2_TX{slash}SWCLK)") (class "Default")
      (node (ref "JP2") (pin "3") (pinfunction "3_3") (pintype "passive"))
      (node (ref "U$2") (pin "37") (pinfunction "PA14/USART2_TX/SWCLK_37") (pintype "bidirectional"))
    )
    (net (code "126") (name "Net-(U$2-PA15{slash}USART2_RX)") (class "Default")
      (node (ref "U$2") (pin "38") (pinfunction "PA15/USART2_RX_38") (pintype "bidirectional"))
      (node (ref "X7") (pin "TP") (pinfunction "TP_TP") (pintype "input"))
    )
    (net (code "127") (name "Net-(U$2-PB3{slash}SPI1_SCK{slash}TIM2_CH2)") (class "Default")
      (node (ref "U$2") (pin "39") (pinfunction "PB3/SPI1_SCK/TIM2_CH2_39") (pintype "bidirectional"))
      (node (ref "X8") (pin "TP") (pinfunction "TP_TP") (pintype "input"))
    )
    (net (code "128") (name "Net-(U$2-PF0{slash}OSC_IN)") (class "Default")
      (node (ref "C1") (pin "2") (pinfunction "2_2") (pintype "passive"))
      (node (ref "U$2") (pin "5") (pinfunction "PF0/OSC_IN_5") (pintype "bidirectional"))
      (node (ref "X1") (pin "P$1") (pinfunction "P$1_P$1") (pintype "bidirectional"))
    )
    (net (code "129") (name "Net-(U$2-PF1{slash}OSC_OUT)") (class "Default")
      (node (ref "C2") (pin "2") (pinfunction "2_2") (pintype "passive"))
      (node (ref "U$2") (pin "6") (pinfunction "PF1/OSC_OUT_6") (pintype "bidirectional"))
      (node (ref "X1") (pin "P$2") (pinfunction "P$2_P$2") (pintype "bidirectional"))
    )
    (net (code "130") (name "Net-(U$6-M)") (class "Default")
      (node (ref "R21") (pin "2") (pinfunction "2_2") (pintype "passive"))
      (node (ref "U$6") (pin "N") (pinfunction "M_N") (pintype "bidirectional"))
    )
    (net (code "131") (name "Net-(U$10-BOOT0)") (class "Default")
      (node (ref "R40") (pin "1") (pinfunction "1_1") (pintype "passive"))
      (node (ref "U$10") (pin "1") (pinfunction "BOOT0_1") (pintype "bidirectional"))
    )
    (net (code "132") (name "Net-(U$10-PA3)") (class "Default")
      (node (ref "LED3") (pin "A") (pinfunction "A_A") (pintype "passive"))
      (node (ref "U$10") (pin "9") (pinfunction "PA3_9") (pintype "bidirectional"))
    )
    (net (code "133") (name "Net-(U$10-PA4)") (class "Default")
      (node (ref "LED4") (pin "A") (pinfunction "A_A") (pintype "passive"))
      (node (ref "U$10") (pin "10") (pinfunction "PA4_10") (pintype "bidirectional"))
    )
    (net (code "134") (name "Net-(U$10-PA6)") (class "Default")
      (node (ref "R29") (pin "2") (pinfunction "2_2") (pintype "passive"))
      (node (ref "U$10") (pin "12") (pinfunction "PA6_12") (pintype "bidirectional"))
    )
    (net (code "135") (name "Net-(U$10-PA7)") (class "Default")
      (node (ref "R28") (pin "2") (pinfunction "2_2") (pintype "passive"))
      (node (ref "U$10") (pin "13") (pinfunction "PA7_13") (pintype "bidirectional"))
    )
    (net (code "136") (name "Net-(U$10-PA9)") (class "Default")
      (node (ref "R30") (pin "2") (pinfunction "2_2") (pintype "passive"))
      (node (ref "U$10") (pin "17") (pinfunction "PA9_17") (pintype "bidirectional"))
    )
    (net (code "137") (name "Net-(U$10-PA10)") (class "Default")
      (node (ref "R31") (pin "2") (pinfunction "2_2") (pintype "passive"))
      (node (ref "U$10") (pin "18") (pinfunction "PA10_18") (pintype "bidirectional"))
    )
    (net (code "138") (name "Net-(U$10-PA13{slash}SWDIO)") (class "Default")
      (node (ref "JP5") (pin "1") (pinfunction "1_1") (pintype "passive"))
      (node (ref "U$10") (pin "19") (pinfunction "PA13/SWDIO_19") (pintype "bidirectional"))
    )
    (net (code "139") (name "Net-(U$10-PA14{slash}SWCLK)") (class "Default")
      (node (ref "JP5") (pin "3") (pinfunction "3_3") (pintype "passive"))
      (node (ref "U$10") (pin "20") (pinfunction "PA14/SWCLK_20") (pintype "bidirectional"))
    )
    (net (code "140") (name "Net-(U$10-PF1{slash}OSCO)") (class "Default")
      (node (ref "K4") (pin "1A") (pinfunction "1A_1A") (pintype "bidirectional"))
      (node (ref "R42") (pin "1") (pinfunction "1_1") (pintype "passive"))
      (node (ref "U$10") (pin "3") (pinfunction "PF1/OSCO_3") (pintype "bidirectional"))
    )
    (net (code "141") (name "Net-(U$10-~{RST})") (class "Default")
      (node (ref "JP5") (pin "2") (pinfunction "2_2") (pintype "passive"))
      (node (ref "R41") (pin "1") (pinfunction "1_1") (pintype "passive"))
      (node (ref "U$10") (pin "4") (pinfunction "~{RST}_4") (pintype "bidirectional"))
    )
    (net (code "142") (name "Net-(U$11-IN1+)") (class "Default")
      (node (ref "C32") (pin "+") (pinfunction "+_+") (pintype "passive"))
      (node (ref "R44") (pin "1") (pinfunction "1_1") (pintype "passive"))
      (node (ref "R45") (pin "2") (pinfunction "2_2") (pintype "passive"))
      (node (ref "U$11") (pin "3") (pinfunction "IN1+_3") (pintype "bidirectional"))
      (node (ref "U$11") (pin "5") (pinfunction "IN2+_5") (pintype "bidirectional"))
    )
    (net (code "143") (name "Net-(U$11-IN1-)") (class "Default")
      (node (ref "R54") (pin "2") (pinfunction "2_2") (pintype "passive"))
      (node (ref "R60") (pin "1") (pinfunction "1_1") (pintype "passive"))
      (node (ref "U$11") (pin "2") (pinfunction "IN1-_2") (pintype "bidirectional"))
    )
    (net (code "144") (name "Net-(U$11-IN2-)") (class "Default")
      (node (ref "R55") (pin "2") (pinfunction "2_2") (pintype "passive"))
      (node (ref "R61") (pin "1") (pinfunction "1_1") (pintype "passive"))
      (node (ref "U$11") (pin "6") (pinfunction "IN2-_6") (pintype "bidirectional"))
    )
    (net (code "145") (name "Net-(U$11-OUT1)") (class "Default")
      (node (ref "C47") (pin "+") (pinfunction "+_+") (pintype "passive"))
      (node (ref "R60") (pin "2") (pinfunction "2_2") (pintype "passive"))
      (node (ref "U$11") (pin "1") (pinfunction "OUT1_1") (pintype "bidirectional"))
    )
    (net (code "146") (name "Net-(U$11-OUT2)") (class "Default")
      (node (ref "C48") (pin "+") (pinfunction "+_+") (pintype "passive"))
      (node (ref "R61") (pin "2") (pinfunction "2_2") (pintype "passive"))
      (node (ref "U$11") (pin "7") (pinfunction "OUT2_7") (pintype "bidirectional"))
    )
    (net (code "147") (name "Net-(USB-BUSJ)") (class "Default")
      (node (ref "C34") (pin "2") (pinfunction "2_2") (pintype "passive"))
      (node (ref "USB") (pin "13") (pinfunction "VD33_13") (pintype "bidirectional"))
      (node (ref "USB") (pin "17") (pinfunction "XRSTJ_17") (pintype "bidirectional"))
      (node (ref "USB") (pin "18") (pinfunction "VBUSM_18") (pintype "bidirectional"))
      (node (ref "USB") (pin "19") (pinfunction "BUSJ_19") (pintype "bidirectional"))
      (node (ref "USB") (pin "21") (pinfunction "VD33_O_21") (pintype "bidirectional"))
      (node (ref "USB") (pin "26") (pinfunction "OVCJ_26") (pintype "bidirectional"))
    )
    (net (code "148") (name "Net-(USB-DM1)") (class "Default")
      (node (ref "USB") (pin "10") (pinfunction "DM1_10") (pintype "bidirectional"))
      (node (ref "USB1") (pin "D-") (pinfunction "D-_D-") (pintype "bidirectional"))
    )
    (net (code "149") (name "Net-(USB-DM2)") (class "Default")
      (node (ref "USB") (pin "8") (pinfunction "DM2_8") (pintype "bidirectional"))
      (node (ref "USB2") (pin "D-") (pinfunction "D-_D-") (pintype "bidirectional"))
    )
    (net (code "150") (name "Net-(USB-DP1)") (class "Default")
      (node (ref "USB") (pin "11") (pinfunction "DP1_11") (pintype "bidirectional"))
      (node (ref "USB1") (pin "D+") (pinfunction "D+_D+") (pintype "bidirectional"))
    )
    (net (code "151") (name "Net-(USB-DP2)") (class "Default")
      (node (ref "USB") (pin "9") (pinfunction "DP2_9") (pintype "bidirectional"))
      (node (ref "USB2") (pin "D+") (pinfunction "D+_D+") (pintype "bidirectional"))
    )
    (net (code "152") (name "Net-(USB-REXT)") (class "Default")
      (node (ref "R50") (pin "2") (pinfunction "2_2") (pintype "passive"))
      (node (ref "USB") (pin "14") (pinfunction "REXT_14") (pintype "bidirectional"))
    )
    (net (code "153") (name "Net-(USB-VD18)") (class "Default")
      (node (ref "C33") (pin "2") (pinfunction "2_2") (pintype "passive"))
      (node (ref "USB") (pin "12") (pinfunction "VD18_O_12") (pintype "bidirectional"))
      (node (ref "USB") (pin "28") (pinfunction "VD18_28") (pintype "bidirectional"))
    )
    (net (code "154") (name "Net-(USB-VDD5)") (class "Default")
      (node (ref "C35") (pin "2") (pinfunction "2_2") (pintype "passive"))
      (node (ref "R51") (pin "1") (pinfunction "1_1") (pintype "passive"))
      (node (ref "USB") (pin "20") (pinfunction "VDD5_20") (pintype "bidirectional"))
    )
    (net (code "155") (name "Net-(USB-XIN)") (class "Default")
      (node (ref "C37") (pin "2") (pinfunction "2_2") (pintype "passive"))
      (node (ref "USB") (pin "3") (pinfunction "XIN_3") (pintype "bidirectional"))
      (node (ref "X9") (pin "P$2") (pinfunction "P$2_P$2") (pintype "bidirectional"))
    )
    (net (code "156") (name "Net-(USB-XOUT)") (class "Default")
      (node (ref "C31") (pin "2") (pinfunction "2_2") (pintype "passive"))
      (node (ref "USB") (pin "2") (pinfunction "XOUT_2") (pintype "bidirectional"))
      (node (ref "X9") (pin "P$1") (pinfunction "P$1_P$1") (pintype "bidirectional"))
    )
    (net (code "157") (name "VCC") (class "Default")
      (node (ref "C10") (pin "1") (pinfunction "1_1") (pintype "passive"))
      (node (ref "C6") (pin "1") (pinfunction "1_1") (pintype "passive"))
      (node (ref "C8") (pin "1") (pinfunction "1_1") (pintype "passive"))
      (node (ref "C9") (pin "1") (pinfunction "1_1") (pintype "passive"))
      (node (ref "IC3") (pin "2") (pinfunction "OUT_2") (pintype "output"))
      (node (ref "IC7") (pin "8") (pinfunction "VDD_8") (pintype "power_in"))
      (node (ref "JP2") (pin "4") (pinfunction "4_4") (pintype "passive"))
      (node (ref "R1") (pin "2") (pinfunction "2_2") (pintype "passive"))
      (node (ref "R12") (pin "2") (pinfunction "2_2") (pintype "passive"))
      (node (ref "R13") (pin "2") (pinfunction "2_2") (pintype "passive"))
      (node (ref "R14") (pin "2") (pinfunction "2_2") (pintype "passive"))
      (node (ref "R15") (pin "2") (pinfunction "2_2") (pintype "passive"))
      (node (ref "R16") (pin "1") (pinfunction "1_1") (pintype "passive"))
      (node (ref "R17") (pin "1") (pinfunction "1_1") (pintype "passive"))
      (node (ref "R18") (pin "1") (pinfunction "1_1") (pintype "passive"))
      (node (ref "R9") (pin "1") (pinfunction "1_1") (pintype "passive"))
      (node (ref "U$2") (pin "1") (pinfunction "VBATT(P1)_1") (pintype "bidirectional"))
      (node (ref "U$2") (pin "24") (pinfunction "VDD_1(P24)_24") (pintype "bidirectional"))
      (node (ref "U$2") (pin "36") (pinfunction "VDDIO2(P36)_36") (pintype "bidirectional"))
      (node (ref "U$2") (pin "48") (pinfunction "VDD_2(P48)_48") (pintype "bidirectional"))
      (node (ref "U$2") (pin "9") (pinfunction "VDDA(P9)_9") (pintype "bidirectional"))
      (node (ref "VDD") (pin "TP") (pinfunction "TP_TP") (pintype "input"))
    )
    (net (code "158") (name "VDD") (class "Default")
      (node (ref "C23") (pin "1") (pinfunction "1_1") (pintype "passive"))
      (node (ref "IC8") (pin "8") (pinfunction "VDD_8") (pintype "bidirectional"))
      (node (ref "JP4") (pin "2") (pinfunction "2_2") (pintype "passive"))
      (node (ref "R10") (pin "2") (pinfunction "2_2") (pintype "passive"))
      (node (ref "R11") (pin "2") (pinfunction "2_2") (pintype "passive"))
      (node (ref "U$9") (pin "1") (pinfunction "3V3_1") (pintype "power_in"))
    )
    (net (code "159") (name "unconnected-(IC8-INT-Pad7)") (class "Default")
      (node (ref "IC8") (pin "7") (pinfunction "INT_7") (pintype "bidirectional"))
    )
    (net (code "160") (name "unconnected-(K1-Pad2A)") (class "Default")
      (node (ref "K1") (pin "2A") (pinfunction "2A_2A") (pintype "bidirectional"))
    )
    (net (code "161") (name "unconnected-(K1-Pad2B)") (class "Default")
      (node (ref "K1") (pin "2B") (pinfunction "2B_2B") (pintype "bidirectional"))
    )
    (net (code "162") (name "unconnected-(K2-Pad1B)") (class "Default")
      (node (ref "K2") (pin "1B") (pinfunction "1B_1B") (pintype "bidirectional"))
    )
    (net (code "163") (name "unconnected-(K3-Pad1A)") (class "Default")
      (node (ref "K3") (pin "1A") (pinfunction "1A_1A") (pintype "bidirectional"))
    )
    (net (code "164") (name "unconnected-(K4-Pad1B)") (class "Default")
      (node (ref "K4") (pin "1B") (pinfunction "1B_1B") (pintype "bidirectional"))
    )
    (net (code "165") (name "unconnected-(K4-Pad2A)") (class "Default")
      (node (ref "K4") (pin "2A") (pinfunction "2A_2A") (pintype "bidirectional"))
    )
    (net (code "166") (name "unconnected-(TFT1-SDO-Pad7)") (class "Default")
      (node (ref "TFT1") (pin "7") (pinfunction "SDO_7") (pintype "bidirectional"))
    )
    (net (code "167") (name "unconnected-(U$2-PB2-Pad20)") (class "Default")
      (node (ref "U$2") (pin "20") (pinfunction "PB2_20") (pintype "bidirectional"))
    )
    (net (code "168") (name "unconnected-(U$2-PB7{slash}USART1_RX{slash}I2C1_SDA-Pad43)") (class "Default")
      (node (ref "U$2") (pin "43") (pinfunction "PB7/USART1_RX/I2C1_SDA_43") (pintype "bidirectional"))
    )
    (net (code "169") (name "unconnected-(U$2-PB10{slash}I2C2_SCL{slash}TIM2_CH3{slash}USART3_TX-Pad21)") (class "Default")
      (node (ref "U$2") (pin "21") (pinfunction "PB10/I2C2_SCL/TIM2_CH3/USART3_TX_21") (pintype "bidirectional"))
    )
    (net (code "170") (name "unconnected-(U$2-PB11{slash}I2C2_SDA{slash}TIM2_C4{slash}USART3_RX-Pad22)") (class "Default")
      (node (ref "U$2") (pin "22") (pinfunction "PB11/I2C2_SDA/TIM2_C4/USART3_RX_22") (pintype "bidirectional"))
    )
    (net (code "171") (name "unconnected-(U$2-PB12-Pad25)") (class "Default")
      (node (ref "U$2") (pin "25") (pinfunction "PB12_25") (pintype "bidirectional"))
    )
    (net (code "172") (name "unconnected-(U$9-GEN4{slash}GPIO23-Pad16)") (class "Default")
      (node (ref "U$9") (pin "16") (pinfunction "GEN4/GPIO23_16") (pintype "bidirectional"))
    )
    (net (code "173") (name "unconnected-(U$9-GND-Pad6)") (class "Default")
      (node (ref "U$9") (pin "6") (pinfunction "GND_6") (pintype "power_in"))
    )
    (net (code "174") (name "unconnected-(U$9-GPIO4{slash}GCKL-Pad7)") (class "Default")
      (node (ref "U$9") (pin "7") (pinfunction "GPIO4/GCKL_7") (pintype "bidirectional"))
    )
    (net (code "175") (name "unconnected-(U$9-GPIO5-Pad29)") (class "Default")
      (node (ref "U$9") (pin "29") (pinfunction "GPIO5_29") (pintype "bidirectional"))
    )
    (net (code "176") (name "unconnected-(U$9-GPIO6-Pad31)") (class "Default")
      (node (ref "U$9") (pin "31") (pinfunction "GPIO6_31") (pintype "bidirectional"))
    )
    (net (code "177") (name "unconnected-(U$9-GPIO9{slash}MISO-Pad21)") (class "Default")
      (node (ref "U$9") (pin "21") (pinfunction "GPIO9/MISO_21") (pintype "bidirectional"))
    )
    (net (code "178") (name "unconnected-(U$9-GPIO12-Pad32)") (class "Default")
      (node (ref "U$9") (pin "32") (pinfunction "GPIO12_32") (pintype "bidirectional"))
    )
    (net (code "179") (name "unconnected-(U$9-GPIO16-Pad36)") (class "Default")
      (node (ref "U$9") (pin "36") (pinfunction "GPIO16_36") (pintype "bidirectional"))
    )
    (net (code "180") (name "unconnected-(U$9-GPIO17{slash}GEN0-Pad11)") (class "Default")
      (node (ref "U$9") (pin "11") (pinfunction "GPIO17/GEN0_11") (pintype "bidirectional"))
    )
    (net (code "181") (name "unconnected-(U$9-GPIO20-Pad38)") (class "Default")
      (node (ref "U$9") (pin "38") (pinfunction "GPIO20_38") (pintype "bidirectional"))
    )
    (net (code "182") (name "unconnected-(U$9-GPIO21-Pad40)") (class "Default")
      (node (ref "U$9") (pin "40") (pinfunction "GPIO21_40") (pintype "bidirectional"))
    )
    (net (code "183") (name "unconnected-(U$9-GPIO22{slash}GEN3-Pad15)") (class "Default")
      (node (ref "U$9") (pin "15") (pinfunction "GPIO22/GEN3_15") (pintype "bidirectional"))
    )
    (net (code "184") (name "unconnected-(U$9-ID_SC-Pad28)") (class "Default")
      (node (ref "U$9") (pin "28") (pinfunction "ID_SC_28") (pintype "bidirectional"))
    )
    (net (code "185") (name "unconnected-(U$9-ID_SD-Pad27)") (class "Default")
      (node (ref "U$9") (pin "27") (pinfunction "ID_SD_27") (pintype "bidirectional"))
    )
    (net (code "186") (name "unconnected-(U$9-~{CE}{slash}GPIO7-Pad26)") (class "Default")
      (node (ref "U$9") (pin "26") (pinfunction "~{CE}/GPIO7_26") (pintype "bidirectional"))
    )
    (net (code "187") (name "unconnected-(USB-DRV-Pad22)") (class "Default")
      (node (ref "USB") (pin "22") (pinfunction "DRV_22") (pintype "bidirectional"))
    )
    (net (code "188") (name "unconnected-(USB-LED1-Pad23)") (class "Default")
      (node (ref "USB") (pin "23") (pinfunction "LED1_23") (pintype "bidirectional"))
    )
    (net (code "189") (name "unconnected-(USB-LED2-Pad24)") (class "Default")
      (node (ref "USB") (pin "24") (pinfunction "LED2_24") (pintype "bidirectional"))
    )
    (net (code "190") (name "unconnected-(USB-PWRJ-Pad25)") (class "Default")
      (node (ref "USB") (pin "25") (pinfunction "PWRJ_25") (pintype "bidirectional"))
    )
    (net (code "191") (name "unconnected-(USB-TESTJ-Pad27)") (class "Default")
      (node (ref "USB") (pin "27") (pinfunction "TESTJ_27") (pintype "bidirectional"))
    )
    (net (code "192") (name "unconnected-(X11A-S-Pad1)") (class "Default")
      (node (ref "X11") (pin "1") (pinfunction "S_1") (pintype "passive"))
    )
    (net (code "193") (name "unconnected-(X11B-S-Pad2)") (class "Default")
      (node (ref "X11") (pin "2") (pinfunction "S_2") (pintype "passive"))
    )
    (net (code "194") (name "unconnected-(X11C-S-Pad3)") (class "Default")
      (node (ref "X11") (pin "3") (pinfunction "S_3") (pintype "passive"))
    )
  )
)
